# robotic_arm.net
KiCad netlist of a schematic drawn in EAGLE
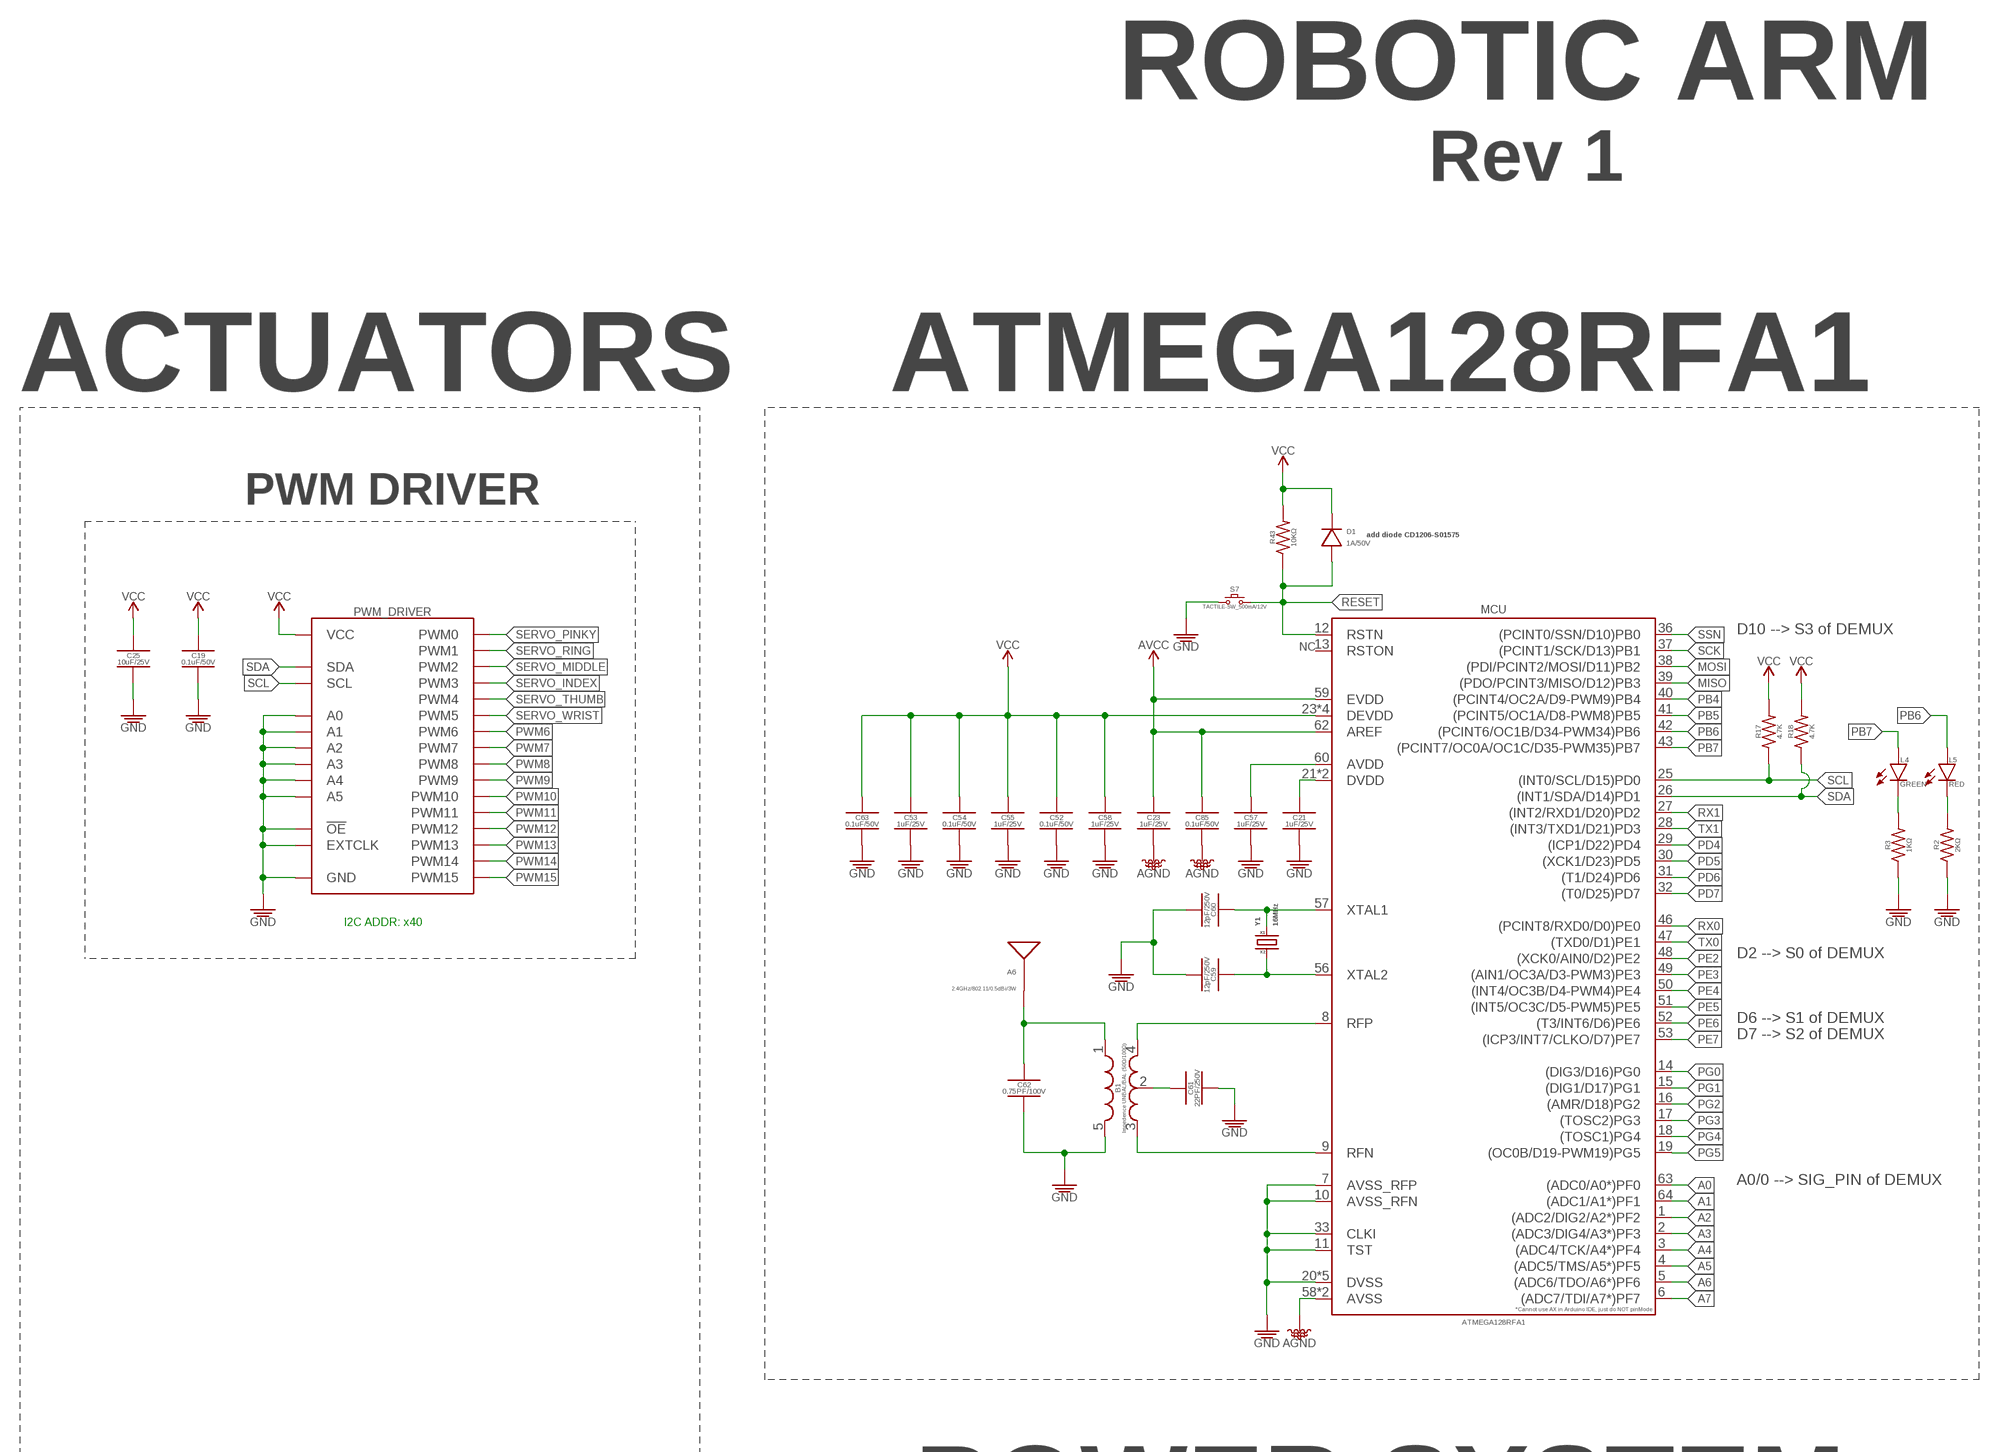
[diagram p0: schematic, sheet 1, part 1 of 3]
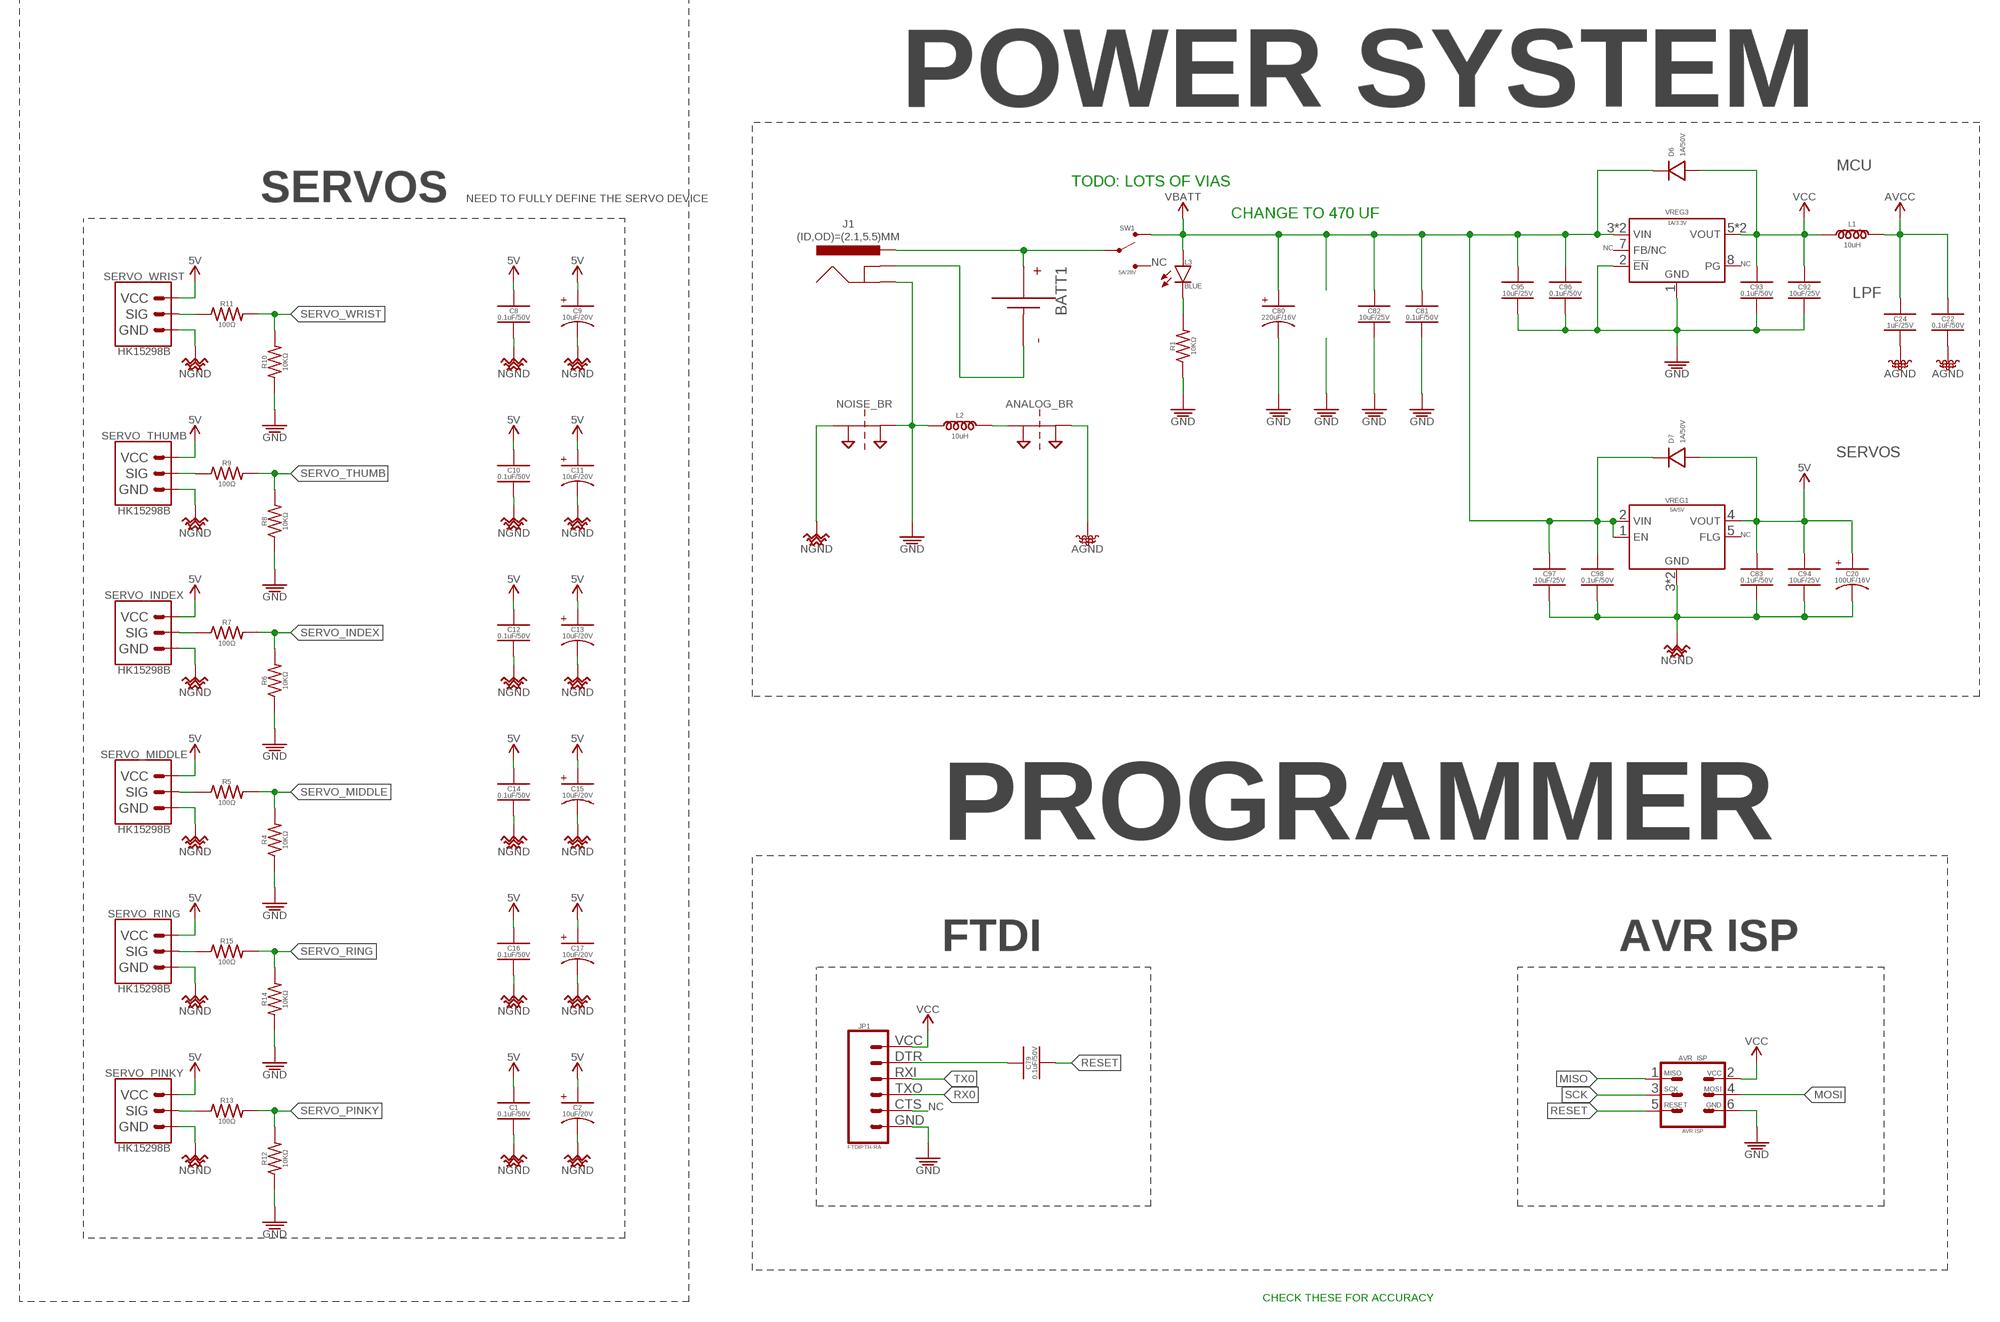
[diagram p1: schematic, sheet 1, part 2 of 3]
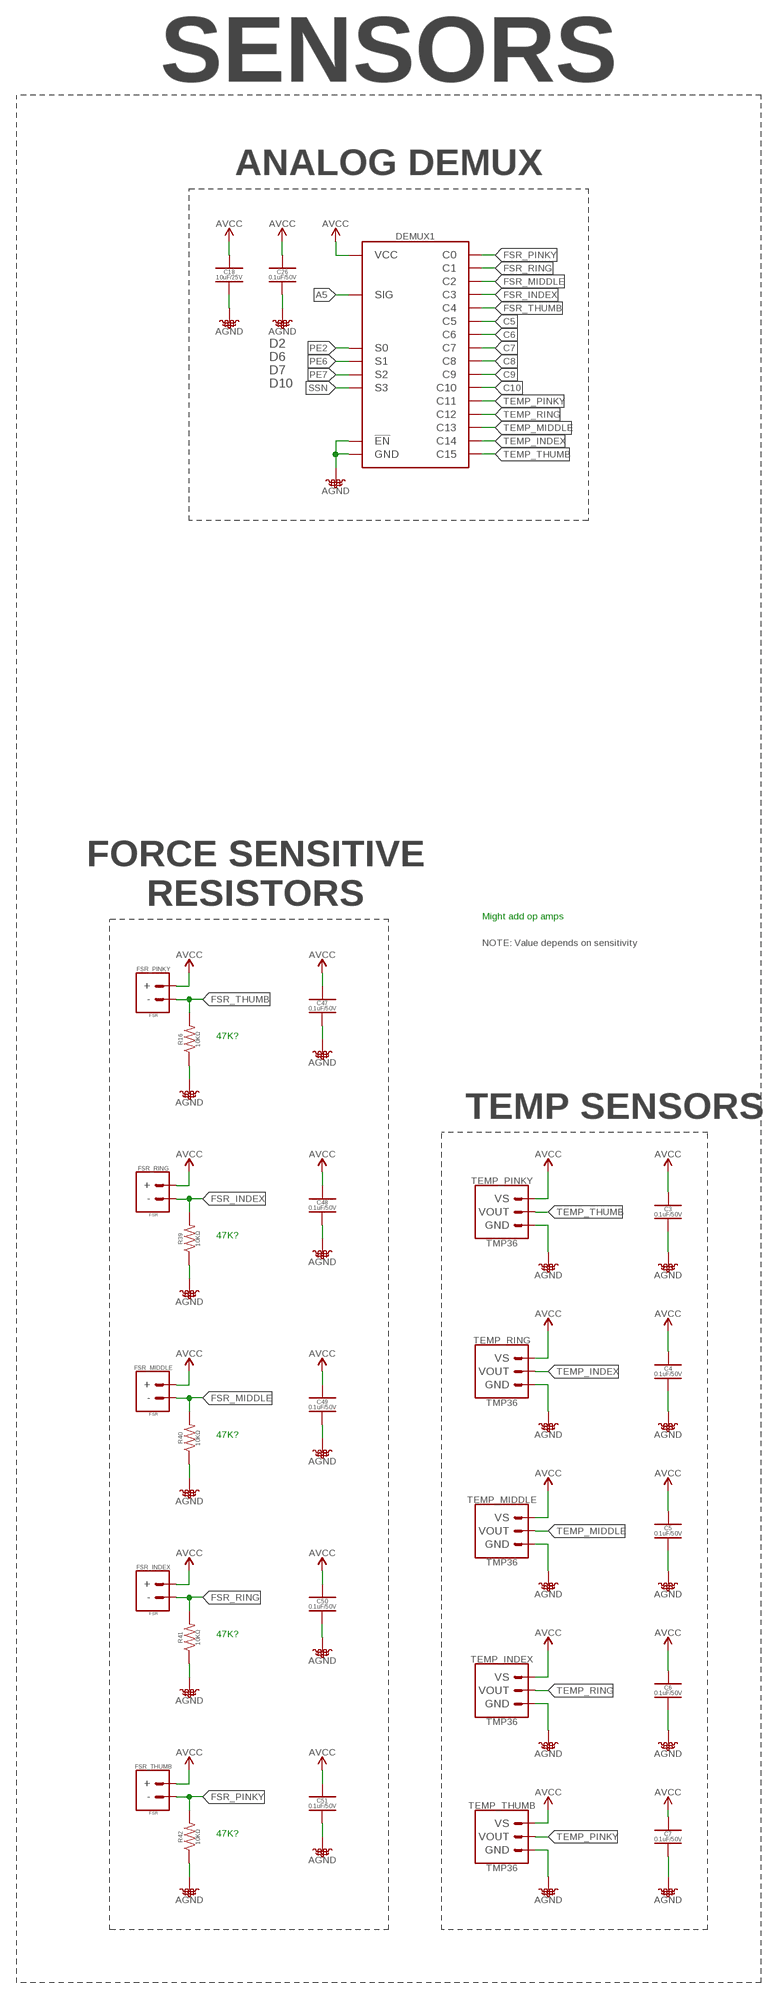
[diagram p2: schematic, sheet 1, part 3 of 3]

(export (version "E")
  (design (tool "Eeschema 10.0.6"))
  (components
    (comp (ref "A6")
      (value "2.4GHz/802.11/0.5dBi/3W")
      (footprint "eagle-import:ANTENNA-CHIP5")
      (fields
        (field (name "MFR") "Linx Technologies Inc.")
        (field (name "MPN") "ANT-2.45-CHP-T")
        (field (name "CREATOR") "Kenmei")
      )
      (libsource (lib "eagle-import") (part "ANTENNA_SMD-CHIP_2.4GHZ-0.5DBI-3W"))
    )
    (comp (ref "ANALOG_BR")
      (value "2PT_GND_TIE")
      (footprint "eagle-import:2PT_GND_TIE")
      (libsource (lib "eagle-import") (part "2PT_GND_TIE"))
    )
    (comp (ref "AVR_ISP")
      (value "AVR ISP")
      (footprint "eagle-import:2X3-NS")
      (fields (field (name "MFR") "Amphenol FCI") (field (name "MPN") "67997-206HLF"))
      (libsource (lib "eagle-import") (part "AVR_SPI_PRG_6NS"))
    )
    (comp (ref "B1")
      (value "Impedence UNBAL/BAL (50Ω/100Ω)")
      (footprint "eagle-import:0805_BALUN")
      (fields
        (field (name "MFR") "Wurth Electronics Inc")
        (field (name "MPN") "748421245")
        (field (name "CREATOR") "Kenmei")
      )
      (libsource (lib "eagle-import") (part "BALUN_SMD-0805_UNBAL/BAL-50/100"))
    )
    (comp (ref "BATT1")
      (value "BATTERYPTH_HOLES")
      (footprint "eagle-import:DUAL_PTH_PADS")
      (libsource (lib "eagle-import") (part "BATTERYPTH_HOLES"))
    )
    (comp (ref "C1")
      (value "0.1uF/50V")
      (footprint "eagle-import:_CER_SMD-805")
      (fields
        (field (name "MFR") "Murata Electronics North America")
        (field (name "MPN") "GRM21BR71H104KA01L")
        (field (name "CREATOR") "MrSwirlyEyes")
      )
      (libsource (lib "eagle-import") (part "0.1UF_SMD-805_50V-10%"))
    )
    (comp (ref "C2")
      (value "10uF/20V")
      (footprint "eagle-import:_TANT_SMD-1206")
      (fields
        (field (name "MFR") "AVX Corporation")
        (field (name "MPN") "TCJA106M020R0150")
        (field (name "CREATOR") "Kenmei")
      )
      (libsource (lib "eagle-import") (part "10UF-POLARIZED_SMD-1206_20V-20%"))
    )
    (comp (ref "C3")
      (value "0.1uF/50V")
      (footprint "eagle-import:_CER_SMD-805")
      (fields
        (field (name "MFR") "Murata Electronics North America")
        (field (name "MPN") "GRM21BR71H104KA01L")
        (field (name "CREATOR") "MrSwirlyEyes")
      )
      (libsource (lib "eagle-import") (part "0.1UF_SMD-805_50V-10%"))
    )
    (comp (ref "C4")
      (value "0.1uF/50V")
      (footprint "eagle-import:_CER_SMD-805")
      (fields
        (field (name "MFR") "Murata Electronics North America")
        (field (name "MPN") "GRM21BR71H104KA01L")
        (field (name "CREATOR") "MrSwirlyEyes")
      )
      (libsource (lib "eagle-import") (part "0.1UF_SMD-805_50V-10%"))
    )
    (comp (ref "C5")
      (value "0.1uF/50V")
      (footprint "eagle-import:_CER_SMD-805")
      (fields
        (field (name "MFR") "Murata Electronics North America")
        (field (name "MPN") "GRM21BR71H104KA01L")
        (field (name "CREATOR") "MrSwirlyEyes")
      )
      (libsource (lib "eagle-import") (part "0.1UF_SMD-805_50V-10%"))
    )
    (comp (ref "C6")
      (value "0.1uF/50V")
      (footprint "eagle-import:_CER_SMD-805")
      (fields
        (field (name "MFR") "Murata Electronics North America")
        (field (name "MPN") "GRM21BR71H104KA01L")
        (field (name "CREATOR") "MrSwirlyEyes")
      )
      (libsource (lib "eagle-import") (part "0.1UF_SMD-805_50V-10%"))
    )
    (comp (ref "C7")
      (value "0.1uF/50V")
      (footprint "eagle-import:_CER_SMD-805")
      (fields
        (field (name "MFR") "Murata Electronics North America")
        (field (name "MPN") "GRM21BR71H104KA01L")
        (field (name "CREATOR") "MrSwirlyEyes")
      )
      (libsource (lib "eagle-import") (part "0.1UF_SMD-805_50V-10%"))
    )
    (comp (ref "C8")
      (value "0.1uF/50V")
      (footprint "eagle-import:_CER_SMD-805")
      (fields
        (field (name "MFR") "Murata Electronics North America")
        (field (name "MPN") "GRM21BR71H104KA01L")
        (field (name "CREATOR") "MrSwirlyEyes")
      )
      (libsource (lib "eagle-import") (part "0.1UF_SMD-805_50V-10%"))
    )
    (comp (ref "C9")
      (value "10uF/20V")
      (footprint "eagle-import:_TANT_SMD-1206")
      (fields
        (field (name "MFR") "AVX Corporation")
        (field (name "MPN") "TCJA106M020R0150")
        (field (name "CREATOR") "Kenmei")
      )
      (libsource (lib "eagle-import") (part "10UF-POLARIZED_SMD-1206_20V-20%"))
    )
    (comp (ref "C10")
      (value "0.1uF/50V")
      (footprint "eagle-import:_CER_SMD-805")
      (fields
        (field (name "MFR") "Murata Electronics North America")
        (field (name "MPN") "GRM21BR71H104KA01L")
        (field (name "CREATOR") "MrSwirlyEyes")
      )
      (libsource (lib "eagle-import") (part "0.1UF_SMD-805_50V-10%"))
    )
    (comp (ref "C11")
      (value "10uF/20V")
      (footprint "eagle-import:_TANT_SMD-1206")
      (fields
        (field (name "MFR") "AVX Corporation")
        (field (name "MPN") "TCJA106M020R0150")
        (field (name "CREATOR") "Kenmei")
      )
      (libsource (lib "eagle-import") (part "10UF-POLARIZED_SMD-1206_20V-20%"))
    )
    (comp (ref "C12")
      (value "0.1uF/50V")
      (footprint "eagle-import:_CER_SMD-805")
      (fields
        (field (name "MFR") "Murata Electronics North America")
        (field (name "MPN") "GRM21BR71H104KA01L")
        (field (name "CREATOR") "MrSwirlyEyes")
      )
      (libsource (lib "eagle-import") (part "0.1UF_SMD-805_50V-10%"))
    )
    (comp (ref "C13")
      (value "10uF/20V")
      (footprint "eagle-import:_TANT_SMD-1206")
      (fields
        (field (name "MFR") "AVX Corporation")
        (field (name "MPN") "TCJA106M020R0150")
        (field (name "CREATOR") "Kenmei")
      )
      (libsource (lib "eagle-import") (part "10UF-POLARIZED_SMD-1206_20V-20%"))
    )
    (comp (ref "C14")
      (value "0.1uF/50V")
      (footprint "eagle-import:_CER_SMD-805")
      (fields
        (field (name "MFR") "Murata Electronics North America")
        (field (name "MPN") "GRM21BR71H104KA01L")
        (field (name "CREATOR") "MrSwirlyEyes")
      )
      (libsource (lib "eagle-import") (part "0.1UF_SMD-805_50V-10%"))
    )
    (comp (ref "C15")
      (value "10uF/20V")
      (footprint "eagle-import:_TANT_SMD-1206")
      (fields
        (field (name "MFR") "AVX Corporation")
        (field (name "MPN") "TCJA106M020R0150")
        (field (name "CREATOR") "Kenmei")
      )
      (libsource (lib "eagle-import") (part "10UF-POLARIZED_SMD-1206_20V-20%"))
    )
    (comp (ref "C16")
      (value "0.1uF/50V")
      (footprint "eagle-import:_CER_SMD-805")
      (fields
        (field (name "MFR") "Murata Electronics North America")
        (field (name "MPN") "GRM21BR71H104KA01L")
        (field (name "CREATOR") "MrSwirlyEyes")
      )
      (libsource (lib "eagle-import") (part "0.1UF_SMD-805_50V-10%"))
    )
    (comp (ref "C17")
      (value "10uF/20V")
      (footprint "eagle-import:_TANT_SMD-1206")
      (fields
        (field (name "MFR") "AVX Corporation")
        (field (name "MPN") "TCJA106M020R0150")
        (field (name "CREATOR") "Kenmei")
      )
      (libsource (lib "eagle-import") (part "10UF-POLARIZED_SMD-1206_20V-20%"))
    )
    (comp (ref "C18")
      (value "10uF/25V")
      (footprint "eagle-import:_CER_SMD-805")
      (fields
        (field (name "MFR") "Murata Electronics North America")
        (field (name "MPN") "GRM21BR61E106KA73K")
        (field (name "CREATOR") "MrSwirlyEyes")
      )
      (libsource (lib "eagle-import") (part "10UF_CER_SMD-805_25V-10%"))
    )
    (comp (ref "C19")
      (value "0.1uF/50V")
      (footprint "eagle-import:_CER_SMD-805")
      (fields
        (field (name "MFR") "Murata Electronics North America")
        (field (name "MPN") "GRM21BR71H104KA01L")
        (field (name "CREATOR") "MrSwirlyEyes")
      )
      (libsource (lib "eagle-import") (part "0.1UF_SMD-805_50V-10%"))
    )
    (comp (ref "C20")
      (value "100UF/16V")
      (footprint "eagle-import:_AE_SMD_L6.6-W6.6")
      (fields
        (field (name "MFR") "Panasonic Electronic Components")
        (field (name "MPN") "EEE-FK1C101P")
        (field (name "CREATOR") "MrSwirlyEyes")
      )
      (libsource (lib "eagle-import") (part "100UF-POLARIZED_SMD_16V-20%"))
    )
    (comp (ref "C21")
      (value "1uF/25V")
      (footprint "eagle-import:_CER_SMD-805")
      (fields
        (field (name "MFR") "Murata Electronics North America ")
        (field (name "MPN") "GRM216R61E105KA12D ")
        (field (name "CREATOR") "Kenmei")
      )
      (libsource (lib "eagle-import") (part "1UF_SMD-805_25V-10%"))
    )
    (comp (ref "C22")
      (value "0.1uF/50V")
      (footprint "eagle-import:_CER_SMD-805")
      (fields
        (field (name "MFR") "Murata Electronics North America")
        (field (name "MPN") "GRM21BR71H104KA01L")
        (field (name "CREATOR") "MrSwirlyEyes")
      )
      (libsource (lib "eagle-import") (part "0.1UF_SMD-805_50V-10%"))
    )
    (comp (ref "C23")
      (value "1uF/25V")
      (footprint "eagle-import:_CER_SMD-805")
      (fields
        (field (name "MFR") "Murata Electronics North America ")
        (field (name "MPN") "GRM216R61E105KA12D ")
        (field (name "CREATOR") "Kenmei")
      )
      (libsource (lib "eagle-import") (part "1UF_SMD-805_25V-10%"))
    )
    (comp (ref "C24")
      (value "1uF/25V")
      (footprint "eagle-import:_CER_SMD-805")
      (fields
        (field (name "MFR") "Murata Electronics North America ")
        (field (name "MPN") "GRM216R61E105KA12D ")
        (field (name "CREATOR") "Kenmei")
      )
      (libsource (lib "eagle-import") (part "1UF_SMD-805_25V-10%"))
    )
    (comp (ref "C25")
      (value "10uF/25V")
      (footprint "eagle-import:_CER_SMD-805")
      (fields
        (field (name "MFR") "Murata Electronics North America")
        (field (name "MPN") "GRM21BR61E106KA73K")
        (field (name "CREATOR") "MrSwirlyEyes")
      )
      (libsource (lib "eagle-import") (part "10UF_CER_SMD-805_25V-10%"))
    )
    (comp (ref "C26")
      (value "0.1uF/50V")
      (footprint "eagle-import:_CER_SMD-805")
      (fields
        (field (name "MFR") "Murata Electronics North America")
        (field (name "MPN") "GRM21BR71H104KA01L")
        (field (name "CREATOR") "MrSwirlyEyes")
      )
      (libsource (lib "eagle-import") (part "0.1UF_SMD-805_50V-10%"))
    )
    (comp (ref "C47")
      (value "0.1uF/50V")
      (footprint "eagle-import:_CER_SMD-805")
      (fields
        (field (name "MFR") "Murata Electronics North America")
        (field (name "MPN") "GRM21BR71H104KA01L")
        (field (name "CREATOR") "MrSwirlyEyes")
      )
      (libsource (lib "eagle-import") (part "0.1UF_SMD-805_50V-10%"))
    )
    (comp (ref "C48")
      (value "0.1uF/50V")
      (footprint "eagle-import:_CER_SMD-805")
      (fields
        (field (name "MFR") "Murata Electronics North America")
        (field (name "MPN") "GRM21BR71H104KA01L")
        (field (name "CREATOR") "MrSwirlyEyes")
      )
      (libsource (lib "eagle-import") (part "0.1UF_SMD-805_50V-10%"))
    )
    (comp (ref "C49")
      (value "0.1uF/50V")
      (footprint "eagle-import:_CER_SMD-805")
      (fields
        (field (name "MFR") "Murata Electronics North America")
        (field (name "MPN") "GRM21BR71H104KA01L")
        (field (name "CREATOR") "MrSwirlyEyes")
      )
      (libsource (lib "eagle-import") (part "0.1UF_SMD-805_50V-10%"))
    )
    (comp (ref "C50")
      (value "0.1uF/50V")
      (footprint "eagle-import:_CER_SMD-805")
      (fields
        (field (name "MFR") "Murata Electronics North America")
        (field (name "MPN") "GRM21BR71H104KA01L")
        (field (name "CREATOR") "MrSwirlyEyes")
      )
      (libsource (lib "eagle-import") (part "0.1UF_SMD-805_50V-10%"))
    )
    (comp (ref "C51")
      (value "0.1uF/50V")
      (footprint "eagle-import:_CER_SMD-805")
      (fields
        (field (name "MFR") "Murata Electronics North America")
        (field (name "MPN") "GRM21BR71H104KA01L")
        (field (name "CREATOR") "MrSwirlyEyes")
      )
      (libsource (lib "eagle-import") (part "0.1UF_SMD-805_50V-10%"))
    )
    (comp (ref "C52")
      (value "0.1uF/50V")
      (footprint "eagle-import:_CER_SMD-805")
      (fields
        (field (name "MFR") "Murata Electronics North America")
        (field (name "MPN") "GRM21BR71H104KA01L")
        (field (name "CREATOR") "MrSwirlyEyes")
      )
      (libsource (lib "eagle-import") (part "0.1UF_SMD-805_50V-10%"))
    )
    (comp (ref "C53")
      (value "1uF/25V")
      (footprint "eagle-import:_CER_SMD-805")
      (fields
        (field (name "MFR") "Murata Electronics North America ")
        (field (name "MPN") "GRM216R61E105KA12D ")
        (field (name "CREATOR") "Kenmei")
      )
      (libsource (lib "eagle-import") (part "1UF_SMD-805_25V-10%"))
    )
    (comp (ref "C54")
      (value "0.1uF/50V")
      (footprint "eagle-import:_CER_SMD-805")
      (fields
        (field (name "MFR") "Murata Electronics North America")
        (field (name "MPN") "GRM21BR71H104KA01L")
        (field (name "CREATOR") "MrSwirlyEyes")
      )
      (libsource (lib "eagle-import") (part "0.1UF_SMD-805_50V-10%"))
    )
    (comp (ref "C55")
      (value "1uF/25V")
      (footprint "eagle-import:_CER_SMD-805")
      (fields
        (field (name "MFR") "Murata Electronics North America ")
        (field (name "MPN") "GRM216R61E105KA12D ")
        (field (name "CREATOR") "Kenmei")
      )
      (libsource (lib "eagle-import") (part "1UF_SMD-805_25V-10%"))
    )
    (comp (ref "C57")
      (value "1uF/25V")
      (footprint "eagle-import:_CER_SMD-805")
      (fields
        (field (name "MFR") "Murata Electronics North America ")
        (field (name "MPN") "GRM216R61E105KA12D ")
        (field (name "CREATOR") "Kenmei")
      )
      (libsource (lib "eagle-import") (part "1UF_SMD-805_25V-10%"))
    )
    (comp (ref "C58")
      (value "1uF/25V")
      (footprint "eagle-import:_CER_SMD-805")
      (fields
        (field (name "MFR") "Murata Electronics North America ")
        (field (name "MPN") "GRM216R61E105KA12D ")
        (field (name "CREATOR") "Kenmei")
      )
      (libsource (lib "eagle-import") (part "1UF_SMD-805_25V-10%"))
    )
    (comp (ref "C59")
      (value "12pF/250V")
      (footprint "eagle-import:_CER_SMD-805")
      (fields
        (field (name "MFR") "Murata Electronics North America")
        (field (name "MPN") "GRM21A5C2E120JW01D ")
        (field (name "CREATOR") "Kenmei")
      )
      (libsource (lib "eagle-import") (part "12PF_SMD-805_250V-5%"))
    )
    (comp (ref "C60")
      (value "12pF/250V")
      (footprint "eagle-import:_CER_SMD-805")
      (fields
        (field (name "MFR") "Murata Electronics North America")
        (field (name "MPN") "GRM21A5C2E120JW01D ")
        (field (name "CREATOR") "Kenmei")
      )
      (libsource (lib "eagle-import") (part "12PF_SMD-805_250V-5%"))
    )
    (comp (ref "C61")
      (value "22PF/250V")
      (footprint "eagle-import:_CER_SMD-805")
      (fields
        (field (name "MFR") "Murata Electronics North America ")
        (field (name "MPN") "GRM21A5C2E220JW01D ")
        (field (name "CREATOR") "Kenmei")
      )
      (libsource (lib "eagle-import") (part "22PF_SMD-805_250V-5%"))
    )
    (comp (ref "C62")
      (value "0.75PF/100V")
      (footprint "eagle-import:_CER_SMD-805")
      (fields
        (field (name "MFR") "Murata Electronics North America ")
        (field (name "MPN") "GQM2195C2AR75CB01D ")
        (field (name "CREATOR") "Kenmei")
      )
      (libsource (lib "eagle-import") (part "0.75PF_SMD-805_100V-33%"))
    )
    (comp (ref "C63")
      (value "0.1uF/50V")
      (footprint "eagle-import:_CER_SMD-805")
      (fields
        (field (name "MFR") "Murata Electronics North America")
        (field (name "MPN") "GRM21BR71H104KA01L")
        (field (name "CREATOR") "MrSwirlyEyes")
      )
      (libsource (lib "eagle-import") (part "0.1UF_SMD-805_50V-10%"))
    )
    (comp (ref "C79")
      (value "0.1uF/50V")
      (footprint "eagle-import:_CER_SMD-805")
      (fields
        (field (name "MFR") "Murata Electronics North America")
        (field (name "MPN") "GRM21BR71H104KA01L")
        (field (name "CREATOR") "MrSwirlyEyes")
      )
      (libsource (lib "eagle-import") (part "0.1UF_SMD-805_50V-10%"))
    )
    (comp (ref "C80")
      (value "220uF/16V")
      (footprint "eagle-import:_AE_SMD_L6.6-W6.6")
      (fields
        (field (name "MFR") "Panasonic Electronic Components")
        (field (name "MPN") "EEE-FT1C221AP")
        (field (name "CREATOR") "MrSwirlyEyes")
      )
      (libsource (lib "eagle-import") (part "220UF-POLARIZED_SMD_16V-20%"))
    )
    (comp (ref "C81")
      (value "0.1uF/50V")
      (footprint "eagle-import:_CER_SMD-805")
      (fields
        (field (name "MFR") "Murata Electronics North America")
        (field (name "MPN") "GRM21BR71H104KA01L")
        (field (name "CREATOR") "MrSwirlyEyes")
      )
      (libsource (lib "eagle-import") (part "0.1UF_SMD-805_50V-10%"))
    )
    (comp (ref "C82")
      (value "10uF/25V")
      (footprint "eagle-import:_CER_SMD-805")
      (fields
        (field (name "MFR") "Murata Electronics North America")
        (field (name "MPN") "GRM21BR61E106KA73K")
        (field (name "CREATOR") "MrSwirlyEyes")
      )
      (libsource (lib "eagle-import") (part "10UF_CER_SMD-805_25V-10%"))
    )
    (comp (ref "C83")
      (value "0.1uF/50V")
      (footprint "eagle-import:_CER_SMD-805")
      (fields
        (field (name "MFR") "Murata Electronics North America")
        (field (name "MPN") "GRM21BR71H104KA01L")
        (field (name "CREATOR") "MrSwirlyEyes")
      )
      (libsource (lib "eagle-import") (part "0.1UF_SMD-805_50V-10%"))
    )
    (comp (ref "C85")
      (value "0.1uF/50V")
      (footprint "eagle-import:_CER_SMD-805")
      (fields
        (field (name "MFR") "Murata Electronics North America")
        (field (name "MPN") "GRM21BR71H104KA01L")
        (field (name "CREATOR") "MrSwirlyEyes")
      )
      (libsource (lib "eagle-import") (part "0.1UF_SMD-805_50V-10%"))
    )
    (comp (ref "C92")
      (value "10uF/25V")
      (footprint "eagle-import:_CER_SMD-805")
      (fields
        (field (name "MFR") "Murata Electronics North America")
        (field (name "MPN") "GRM21BR61E106KA73K")
        (field (name "CREATOR") "MrSwirlyEyes")
      )
      (libsource (lib "eagle-import") (part "10UF_CER_SMD-805_25V-10%"))
    )
    (comp (ref "C93")
      (value "0.1uF/50V")
      (footprint "eagle-import:_CER_SMD-805")
      (fields
        (field (name "MFR") "Murata Electronics North America")
        (field (name "MPN") "GRM21BR71H104KA01L")
        (field (name "CREATOR") "MrSwirlyEyes")
      )
      (libsource (lib "eagle-import") (part "0.1UF_SMD-805_50V-10%"))
    )
    (comp (ref "C94")
      (value "10uF/25V")
      (footprint "eagle-import:_CER_SMD-805")
      (fields
        (field (name "MFR") "Murata Electronics North America")
        (field (name "MPN") "GRM21BR61E106KA73K")
        (field (name "CREATOR") "MrSwirlyEyes")
      )
      (libsource (lib "eagle-import") (part "10UF_CER_SMD-805_25V-10%"))
    )
    (comp (ref "C95")
      (value "10uF/25V")
      (footprint "eagle-import:_CER_SMD-805")
      (fields
        (field (name "MFR") "Murata Electronics North America")
        (field (name "MPN") "GRM21BR61E106KA73K")
        (field (name "CREATOR") "MrSwirlyEyes")
      )
      (libsource (lib "eagle-import") (part "10UF_CER_SMD-805_25V-10%"))
    )
    (comp (ref "C96")
      (value "0.1uF/50V")
      (footprint "eagle-import:_CER_SMD-805")
      (fields
        (field (name "MFR") "Murata Electronics North America")
        (field (name "MPN") "GRM21BR71H104KA01L")
        (field (name "CREATOR") "MrSwirlyEyes")
      )
      (libsource (lib "eagle-import") (part "0.1UF_SMD-805_50V-10%"))
    )
    (comp (ref "C97")
      (value "10uF/25V")
      (footprint "eagle-import:_CER_SMD-805")
      (fields
        (field (name "MFR") "Murata Electronics North America")
        (field (name "MPN") "GRM21BR61E106KA73K")
        (field (name "CREATOR") "MrSwirlyEyes")
      )
      (libsource (lib "eagle-import") (part "10UF_CER_SMD-805_25V-10%"))
    )
    (comp (ref "C98")
      (value "0.1uF/50V")
      (footprint "eagle-import:_CER_SMD-805")
      (fields
        (field (name "MFR") "Murata Electronics North America")
        (field (name "MPN") "GRM21BR71H104KA01L")
        (field (name "CREATOR") "MrSwirlyEyes")
      )
      (libsource (lib "eagle-import") (part "0.1UF_SMD-805_50V-10%"))
    )
    (comp (ref "D1")
      (value "1A/50V")
      (footprint "eagle-import:SOD123F")
      (fields
        (field (name "MFR") "Comchip Technology")
        (field (name "MPN") "CGRKM4001-HF")
        (field (name "CREATOR") "MrSwirlyEyes")
      )
      (libsource (lib "eagle-import") (part "DIODE_GENERAL-PURPOSE_SMD_GP_1A-50V"))
    )
    (comp (ref "D6")
      (value "1A/50V")
      (footprint "eagle-import:SOD123F")
      (fields
        (field (name "MFR") "Comchip Technology")
        (field (name "MPN") "CGRKM4001-HF")
        (field (name "CREATOR") "MrSwirlyEyes")
      )
      (libsource (lib "eagle-import") (part "DIODE_GENERAL-PURPOSE_SMD_GP_1A-50V"))
    )
    (comp (ref "D7")
      (value "1A/50V")
      (footprint "eagle-import:SOD123F")
      (fields
        (field (name "MFR") "Comchip Technology")
        (field (name "MPN") "CGRKM4001-HF")
        (field (name "CREATOR") "MrSwirlyEyes")
      )
      (libsource (lib "eagle-import") (part "DIODE_GENERAL-PURPOSE_SMD_GP_1A-50V"))
    )
    (comp (ref "DEMUX1")
      (value "CH16_MUX-DEMUX")
      (footprint "eagle-import:SSOP-24")
      (fields
        (field (name "MFR") "Texas Instruments")
        (field (name "MPN") "CD74HC4067SM96")
        (field (name "CREATOR") "MrSwirlyEyes")
      )
      (libsource (lib "eagle-import") (part "CD74HC4067-SM96_16{colon}1_MUX-DEMUX"))
    )
    (comp (ref "FSR_INDEX")
      (value "FSR")
      (footprint "eagle-import:CONNECTOR_FSR")
      (fields
        (field (name "MFR") "Interlink Electronics")
        (field (name "MPN") "34-00004")
        (field (name "CREATOR") "MrSwirlyEyes")
      )
      (libsource (lib "eagle-import") (part "FSR_FORCE-SENSATIVE-RESISTOR_PRESS-SENSOR"))
    )
    (comp (ref "FSR_MIDDLE")
      (value "FSR")
      (footprint "eagle-import:CONNECTOR_FSR")
      (fields
        (field (name "MFR") "Interlink Electronics")
        (field (name "MPN") "34-00004")
        (field (name "CREATOR") "MrSwirlyEyes")
      )
      (libsource (lib "eagle-import") (part "FSR_FORCE-SENSATIVE-RESISTOR_PRESS-SENSOR"))
    )
    (comp (ref "FSR_PINKY")
      (value "FSR")
      (footprint "eagle-import:CONNECTOR_FSR")
      (fields
        (field (name "MFR") "Interlink Electronics")
        (field (name "MPN") "34-00004")
        (field (name "CREATOR") "MrSwirlyEyes")
      )
      (libsource (lib "eagle-import") (part "FSR_FORCE-SENSATIVE-RESISTOR_PRESS-SENSOR"))
    )
    (comp (ref "FSR_RING")
      (value "FSR")
      (footprint "eagle-import:CONNECTOR_FSR")
      (fields
        (field (name "MFR") "Interlink Electronics")
        (field (name "MPN") "34-00004")
        (field (name "CREATOR") "MrSwirlyEyes")
      )
      (libsource (lib "eagle-import") (part "FSR_FORCE-SENSATIVE-RESISTOR_PRESS-SENSOR"))
    )
    (comp (ref "FSR_THUMB")
      (value "FSR")
      (footprint "eagle-import:CONNECTOR_FSR")
      (fields
        (field (name "MFR") "Interlink Electronics")
        (field (name "MPN") "34-00004")
        (field (name "CREATOR") "MrSwirlyEyes")
      )
      (libsource (lib "eagle-import") (part "FSR_FORCE-SENSATIVE-RESISTOR_PRESS-SENSOR"))
    )
    (comp (ref "J1")
      (value "(ID,OD)=(2.1,5.5)MM")
      (footprint "eagle-import:POWER_JACK_SLOT_ID2.1MM-OD5.5MM")
      (fields
        (field (name "MFR") "MPD (Memory Protection Devices)")
        (field (name "MPN") "EJ508A")
        (field (name "CREATOR") "MrSwirlyEyes")
      )
      (libsource (lib "eagle-import") (part "POWER_JACK-BARREL_ID2.1MM-OD5.5MM"))
    )
    (comp (ref "JP1")
      (value "FTDIPTH-RA")
      (footprint "eagle-import:FTDI_BASIC-6PIN-MALE-RA")
      (fields (field (name "MFR") "Amphenol FCI") (field (name "MPN") "68016-406HLF"))
      (libsource (lib "eagle-import") (part "FTDIPTH-RA"))
    )
    (comp (ref "L1")
      (value "10uH")
      (footprint "eagle-import:_SMD-805")
      (fields
        (field (name "MFR") "Taiyo Yuden")
        (field (name "MPN") "CB2012T100KR")
        (field (name "CREATOR") "MrSwirlyEyes")
      )
      (libsource (lib "eagle-import") (part "10UH_SMD-805_0.5A-0.65OHM-10%"))
    )
    (comp (ref "L2")
      (value "10uH")
      (footprint "eagle-import:_SMD-805")
      (fields
        (field (name "MFR") "Taiyo Yuden")
        (field (name "MPN") "CB2012T100KR")
        (field (name "CREATOR") "MrSwirlyEyes")
      )
      (libsource (lib "eagle-import") (part "10UH_SMD-805_0.5A-0.65OHM-10%"))
    )
    (comp (ref "L3")
      (value "BLUE")
      (footprint "eagle-import:LED_SMD-805_")
      (fields
        (field (name "MFR") "Lite-On Inc.")
        (field (name "MPN") "LTST-C170TBKT")
        (field (name "CREATOR") "MrSwirlyEyes")
      )
      (libsource (lib "eagle-import") (part "LED_SMD-0805_DISCRETE_BLUE"))
    )
    (comp (ref "L4")
      (value "GREEN")
      (footprint "eagle-import:LED_SMD-805_")
      (fields
        (field (name "MFR") "Lite-On Inc.")
        (field (name "MPN") "LTST-C170KGKT")
        (field (name "CREATOR") "MrSwirlyEyes")
      )
      (libsource (lib "eagle-import") (part "LED_SMD-0805_DISCRETE_GREEN"))
    )
    (comp (ref "L5")
      (value "RED")
      (footprint "eagle-import:LED_SMD-805_")
      (fields
        (field (name "MFR") "Lite-On Inc.")
        (field (name "MPN") "LTST-C170KRKT")
        (field (name "CREATOR") "MrSwirlyEyes")
      )
      (libsource (lib "eagle-import") (part "LED_SMD-0805_DISCRETE_RED"))
    )
    (comp (ref "MCU")
      (value "ATMEGA128RFA1")
      (footprint "eagle-import:VFQFN-64")
      (fields
        (field (name "MFR") "Atmel")
        (field (name "MPN") "ATMEGA128RFA1-ZU ")
        (field (name "CREATOR") "Kenmei")
      )
      (libsource (lib "eagle-import") (part "ATMEGA128RFA1_VFQFN-64_EXPOSED-PAD"))
    )
    (comp (ref "NOISE_BR")
      (value "2PT_GND_TIE")
      (footprint "eagle-import:2PT_GND_TIE")
      (libsource (lib "eagle-import") (part "2PT_GND_TIE"))
    )
    (comp (ref "PWM_DRIVER")
      (value "PCA9685")
      (footprint "eagle-import:TSSOP-28")
      (fields
        (field (name "MFR") "NXP USA Inc.")
        (field (name "MPN") "PCA9685PW,118")
        (field (name "CREATOR") "MrSwirlyEyes")
      )
      (libsource (lib "eagle-import") (part "PCA9685_16-CH_12-BIT_PWM-DRIVER"))
    )
    (comp (ref "R1")
      (value "10KΩ")
      (footprint "eagle-import:RESISTOR_SMD-805")
      (fields
        (field (name "MFR") "Yageo")
        (field (name "MPN") "RC0805JR-0710KL")
        (field (name "CREATOR") "Kenmei")
      )
      (libsource (lib "eagle-import") (part "10KΩ_SMD-0805_1/8W-5%"))
    )
    (comp (ref "R2")
      (value "2KΩ")
      (footprint "eagle-import:RESISTOR_SMD-805")
      (fields
        (field (name "MFR") "Yageo")
        (field (name "MPN") "RC0805JR-072KL")
        (field (name "CREATOR") "MrSwirlyEyes")
      )
      (libsource (lib "eagle-import") (part "2KΩ_SMD-0805_1/8W-5%"))
    )
    (comp (ref "R3")
      (value "1KΩ")
      (footprint "eagle-import:RESISTOR_SMD-805")
      (fields
        (field (name "MFR") "Yageo")
        (field (name "MPN") "RC0805JR-071KL ")
        (field (name "CREATOR") "Kenmei")
      )
      (libsource (lib "eagle-import") (part "1KΩ_SMD-0805_1/8W-5%"))
    )
    (comp (ref "R4")
      (value "10KΩ")
      (footprint "eagle-import:RESISTOR_SMD-805")
      (fields
        (field (name "MFR") "Yageo")
        (field (name "MPN") "RC0805JR-0710KL")
        (field (name "CREATOR") "Kenmei")
      )
      (libsource (lib "eagle-import") (part "10KΩ_SMD-0805_1/8W-5%"))
    )
    (comp (ref "R5")
      (value "100Ω")
      (footprint "eagle-import:RESISTOR_SMD-805")
      (fields
        (field (name "MFR") "Yageo")
        (field (name "MPN") "RC0805JR-07100RL")
        (field (name "CREATOR") "Kenmei")
      )
      (libsource (lib "eagle-import") (part "100Ω_SMD-0805_1/8W-5%"))
    )
    (comp (ref "R6")
      (value "10KΩ")
      (footprint "eagle-import:RESISTOR_SMD-805")
      (fields
        (field (name "MFR") "Yageo")
        (field (name "MPN") "RC0805JR-0710KL")
        (field (name "CREATOR") "Kenmei")
      )
      (libsource (lib "eagle-import") (part "10KΩ_SMD-0805_1/8W-5%"))
    )
    (comp (ref "R7")
      (value "100Ω")
      (footprint "eagle-import:RESISTOR_SMD-805")
      (fields
        (field (name "MFR") "Yageo")
        (field (name "MPN") "RC0805JR-07100RL")
        (field (name "CREATOR") "Kenmei")
      )
      (libsource (lib "eagle-import") (part "100Ω_SMD-0805_1/8W-5%"))
    )
    (comp (ref "R8")
      (value "10KΩ")
      (footprint "eagle-import:RESISTOR_SMD-805")
      (fields
        (field (name "MFR") "Yageo")
        (field (name "MPN") "RC0805JR-0710KL")
        (field (name "CREATOR") "Kenmei")
      )
      (libsource (lib "eagle-import") (part "10KΩ_SMD-0805_1/8W-5%"))
    )
    (comp (ref "R9")
      (value "100Ω")
      (footprint "eagle-import:RESISTOR_SMD-805")
      (fields
        (field (name "MFR") "Yageo")
        (field (name "MPN") "RC0805JR-07100RL")
        (field (name "CREATOR") "Kenmei")
      )
      (libsource (lib "eagle-import") (part "100Ω_SMD-0805_1/8W-5%"))
    )
    (comp (ref "R10")
      (value "10KΩ")
      (footprint "eagle-import:RESISTOR_SMD-805")
      (fields
        (field (name "MFR") "Yageo")
        (field (name "MPN") "RC0805JR-0710KL")
        (field (name "CREATOR") "Kenmei")
      )
      (libsource (lib "eagle-import") (part "10KΩ_SMD-0805_1/8W-5%"))
    )
    (comp (ref "R11")
      (value "100Ω")
      (footprint "eagle-import:RESISTOR_SMD-805")
      (fields
        (field (name "MFR") "Yageo")
        (field (name "MPN") "RC0805JR-07100RL")
        (field (name "CREATOR") "Kenmei")
      )
      (libsource (lib "eagle-import") (part "100Ω_SMD-0805_1/8W-5%"))
    )
    (comp (ref "R12")
      (value "10KΩ")
      (footprint "eagle-import:RESISTOR_SMD-805")
      (fields
        (field (name "MFR") "Yageo")
        (field (name "MPN") "RC0805JR-0710KL")
        (field (name "CREATOR") "Kenmei")
      )
      (libsource (lib "eagle-import") (part "10KΩ_SMD-0805_1/8W-5%"))
    )
    (comp (ref "R13")
      (value "100Ω")
      (footprint "eagle-import:RESISTOR_SMD-805")
      (fields
        (field (name "MFR") "Yageo")
        (field (name "MPN") "RC0805JR-07100RL")
        (field (name "CREATOR") "Kenmei")
      )
      (libsource (lib "eagle-import") (part "100Ω_SMD-0805_1/8W-5%"))
    )
    (comp (ref "R14")
      (value "10KΩ")
      (footprint "eagle-import:RESISTOR_SMD-805")
      (fields
        (field (name "MFR") "Yageo")
        (field (name "MPN") "RC0805JR-0710KL")
        (field (name "CREATOR") "Kenmei")
      )
      (libsource (lib "eagle-import") (part "10KΩ_SMD-0805_1/8W-5%"))
    )
    (comp (ref "R15")
      (value "100Ω")
      (footprint "eagle-import:RESISTOR_SMD-805")
      (fields
        (field (name "MFR") "Yageo")
        (field (name "MPN") "RC0805JR-07100RL")
        (field (name "CREATOR") "Kenmei")
      )
      (libsource (lib "eagle-import") (part "100Ω_SMD-0805_1/8W-5%"))
    )
    (comp (ref "R16")
      (value "10KΩ")
      (footprint "eagle-import:RESISTOR_SMD-805")
      (fields
        (field (name "MFR") "Yageo")
        (field (name "MPN") "RC0805JR-0710KL")
        (field (name "CREATOR") "Kenmei")
      )
      (libsource (lib "eagle-import") (part "10KΩ_SMD-0805_1/8W-5%"))
    )
    (comp (ref "R17")
      (value "4.7K")
      (footprint "eagle-import:RESISTOR_SMD-805")
      (fields
        (field (name "MFR") "Yageo")
        (field (name "MPN") "RC0805JR-074K7L")
        (field (name "CREATOR") "MrSwirlyEyes")
      )
      (libsource (lib "eagle-import") (part "4.7KΩ_SMD-0805_1/8W-5%"))
    )
    (comp (ref "R18")
      (value "4.7K")
      (footprint "eagle-import:RESISTOR_SMD-805")
      (fields
        (field (name "MFR") "Yageo")
        (field (name "MPN") "RC0805JR-074K7L")
        (field (name "CREATOR") "MrSwirlyEyes")
      )
      (libsource (lib "eagle-import") (part "4.7KΩ_SMD-0805_1/8W-5%"))
    )
    (comp (ref "R39")
      (value "10KΩ")
      (footprint "eagle-import:RESISTOR_SMD-805")
      (fields
        (field (name "MFR") "Yageo")
        (field (name "MPN") "RC0805JR-0710KL")
        (field (name "CREATOR") "Kenmei")
      )
      (libsource (lib "eagle-import") (part "10KΩ_SMD-0805_1/8W-5%"))
    )
    (comp (ref "R40")
      (value "10KΩ")
      (footprint "eagle-import:RESISTOR_SMD-805")
      (fields
        (field (name "MFR") "Yageo")
        (field (name "MPN") "RC0805JR-0710KL")
        (field (name "CREATOR") "Kenmei")
      )
      (libsource (lib "eagle-import") (part "10KΩ_SMD-0805_1/8W-5%"))
    )
    (comp (ref "R41")
      (value "10KΩ")
      (footprint "eagle-import:RESISTOR_SMD-805")
      (fields
        (field (name "MFR") "Yageo")
        (field (name "MPN") "RC0805JR-0710KL")
        (field (name "CREATOR") "Kenmei")
      )
      (libsource (lib "eagle-import") (part "10KΩ_SMD-0805_1/8W-5%"))
    )
    (comp (ref "R42")
      (value "10KΩ")
      (footprint "eagle-import:RESISTOR_SMD-805")
      (fields
        (field (name "MFR") "Yageo")
        (field (name "MPN") "RC0805JR-0710KL")
        (field (name "CREATOR") "Kenmei")
      )
      (libsource (lib "eagle-import") (part "10KΩ_SMD-0805_1/8W-5%"))
    )
    (comp (ref "R43")
      (value "10KΩ")
      (footprint "eagle-import:RESISTOR_SMD-805")
      (fields
        (field (name "MFR") "Yageo")
        (field (name "MPN") "RC0805JR-0710KL")
        (field (name "CREATOR") "Kenmei")
      )
      (libsource (lib "eagle-import") (part "10KΩ_SMD-0805_1/8W-5%"))
    )
    (comp (ref "S7")
      (value "TACTILE-SW_500mA/12V")
      (footprint "eagle-import:BTN_MOMENTARY_SPST-NO_SMD_12V_50MA_L5.2-W5.2")
      (fields
        (field (name "MFR") "C&K")
        (field (name "MPN") "RS-187R05A2-DS MT RT")
        (field (name "CREATOR") "MrSwirlyEyes")
      )
      (libsource (lib "eagle-import") (part "SWITCH_MOMENTARYSPST-SMD-50MA-12V_L5.2-W5.2"))
    )
    (comp (ref "SERVO_INDEX")
      (value "HK15298B")
      (footprint "eagle-import:CONNECTOR_SERVO")
      (fields (field (name "CREATOR") "MrSwirlyEyes"))
      (libsource (lib "eagle-import") (part "SERVO-HK15298B"))
    )
    (comp (ref "SERVO_MIDDLE")
      (value "HK15298B")
      (footprint "eagle-import:CONNECTOR_SERVO")
      (fields (field (name "CREATOR") "MrSwirlyEyes"))
      (libsource (lib "eagle-import") (part "SERVO-HK15298B"))
    )
    (comp (ref "SERVO_PINKY")
      (value "HK15298B")
      (footprint "eagle-import:CONNECTOR_SERVO")
      (fields (field (name "CREATOR") "MrSwirlyEyes"))
      (libsource (lib "eagle-import") (part "SERVO-HK15298B"))
    )
    (comp (ref "SERVO_RING")
      (value "HK15298B")
      (footprint "eagle-import:CONNECTOR_SERVO")
      (fields (field (name "CREATOR") "MrSwirlyEyes"))
      (libsource (lib "eagle-import") (part "SERVO-HK15298B"))
    )
    (comp (ref "SERVO_THUMB")
      (value "HK15298B")
      (footprint "eagle-import:CONNECTOR_SERVO")
      (fields (field (name "CREATOR") "MrSwirlyEyes"))
      (libsource (lib "eagle-import") (part "SERVO-HK15298B"))
    )
    (comp (ref "SERVO_WRIST")
      (value "HK15298B")
      (footprint "eagle-import:CONNECTOR_SERVO")
      (fields (field (name "CREATOR") "MrSwirlyEyes"))
      (libsource (lib "eagle-import") (part "SERVO-HK15298B"))
    )
    (comp (ref "SW1")
      (value "5A/28V")
      (footprint "eagle-import:SW_TOGGLE_SPDT_5A-28V_13L-7W")
      (fields
        (field (name "MFR") "E-Switch")
        (field (name "MPN") "100SP1T1B4M2QE")
        (field (name "CREATOR") "MrSwirlyEyes")
      )
      (libsource (lib "eagle-import") (part "SWITCH_SPDT_VERT_PTH_5A-28V_13L-7W"))
    )
    (comp (ref "TEMP_INDEX")
      (value "TMP36")
      (footprint "eagle-import:CONNECTOR_TMP36")
      (fields
        (field (name "MFR") "Analog Devices Inc.")
        (field (name "MPN") "TMP36GT9Z")
        (field (name "CREATOR") "MrSwirlyEyes")
      )
      (libsource (lib "eagle-import") (part "TEMPERATURE-SENSOR_TMP36"))
    )
    (comp (ref "TEMP_MIDDLE")
      (value "TMP36")
      (footprint "eagle-import:CONNECTOR_TMP36")
      (fields
        (field (name "MFR") "Analog Devices Inc.")
        (field (name "MPN") "TMP36GT9Z")
        (field (name "CREATOR") "MrSwirlyEyes")
      )
      (libsource (lib "eagle-import") (part "TEMPERATURE-SENSOR_TMP36"))
    )
    (comp (ref "TEMP_PINKY")
      (value "TMP36")
      (footprint "eagle-import:CONNECTOR_TMP36")
      (fields
        (field (name "MFR") "Analog Devices Inc.")
        (field (name "MPN") "TMP36GT9Z")
        (field (name "CREATOR") "MrSwirlyEyes")
      )
      (libsource (lib "eagle-import") (part "TEMPERATURE-SENSOR_TMP36"))
    )
    (comp (ref "TEMP_RING")
      (value "TMP36")
      (footprint "eagle-import:CONNECTOR_TMP36")
      (fields
        (field (name "MFR") "Analog Devices Inc.")
        (field (name "MPN") "TMP36GT9Z")
        (field (name "CREATOR") "MrSwirlyEyes")
      )
      (libsource (lib "eagle-import") (part "TEMPERATURE-SENSOR_TMP36"))
    )
    (comp (ref "TEMP_THUMB")
      (value "TMP36")
      (footprint "eagle-import:CONNECTOR_TMP36")
      (fields
        (field (name "MFR") "Analog Devices Inc.")
        (field (name "MPN") "TMP36GT9Z")
        (field (name "CREATOR") "MrSwirlyEyes")
      )
      (libsource (lib "eagle-import") (part "TEMPERATURE-SENSOR_TMP36"))
    )
    (comp (ref "VREG1")
      (value "5A/5V")
      (footprint "eagle-import:TO-263-5")
      (fields
        (field (name "MFR") "Microchip Technology")
        (field (name "MPN") "MIC29501-5.0WU")
        (field (name "CREATOR") "MrSwirlyEyes")
      )
      (libsource (lib "eagle-import") (part "VREG_MIC29501-5.0_LINEAR_ULDO_5A-5VMIC29501-5.0_5A-5V"))
    )
    (comp (ref "VREG3")
      (value "1A/3.3V")
      (footprint "eagle-import:SOIC-8_W3.9MM")
      (fields
        (field (name "MFR") "Texas Instruments")
        (field (name "MPN") "TPS76833QDR")
        (field (name "CREATOR") "MrSwirlyEyes")
      )
      (libsource (lib "eagle-import") (part "VREG_TPS76833_ULDO_FAST-TRANSIENT_1A-3.3VTPS76833QDR_1A-3.3V"))
    )
    (comp (ref "Y1")
      (value "16MHz")
      (footprint "eagle-import:CRYSTAL-SMD-5X3")
      (fields (field (name "MFR") "Abracon LLC") (field (name "MPN") "ABM3B-16.000MHZ-B2-T"))
      (libsource (lib "eagle-import") (part "CRYSTAL_ABM3B_16MHZ_18PF"))
    )
  )
  (nets
    (net (code "1") (name "5V") (class "Default")
      (node (ref "C1") (pin "1") (pinfunction "1_1") (pintype "passive"))
      (node (ref "C10") (pin "1") (pinfunction "1_1") (pintype "passive"))
      (node (ref "C11") (pin "+") (pinfunction "A_+") (pintype "passive"))
      (node (ref "C12") (pin "1") (pinfunction "1_1") (pintype "passive"))
      (node (ref "C13") (pin "+") (pinfunction "A_+") (pintype "passive"))
      (node (ref "C14") (pin "1") (pinfunction "1_1") (pintype "passive"))
      (node (ref "C15") (pin "+") (pinfunction "A_+") (pintype "passive"))
      (node (ref "C16") (pin "1") (pinfunction "1_1") (pintype "passive"))
      (node (ref "C17") (pin "+") (pinfunction "A_+") (pintype "passive"))
      (node (ref "C2") (pin "+") (pinfunction "A_+") (pintype "passive"))
      (node (ref "C20") (pin "A") (pinfunction "A_A") (pintype "passive"))
      (node (ref "C8") (pin "1") (pinfunction "1_1") (pintype "passive"))
      (node (ref "C83") (pin "1") (pinfunction "1_1") (pintype "passive"))
      (node (ref "C9") (pin "+") (pinfunction "A_+") (pintype "passive"))
      (node (ref "C94") (pin "1") (pinfunction "1_1") (pintype "passive"))
      (node (ref "D7") (pin "A") (pinfunction "A_A") (pintype "passive"))
      (node (ref "SERVO_INDEX") (pin "2") (pinfunction "VCC_2") (pintype "passive"))
      (node (ref "SERVO_MIDDLE") (pin "2") (pinfunction "VCC_2") (pintype "passive"))
      (node (ref "SERVO_PINKY") (pin "2") (pinfunction "VCC_2") (pintype "passive"))
      (node (ref "SERVO_RING") (pin "2") (pinfunction "VCC_2") (pintype "passive"))
      (node (ref "SERVO_THUMB") (pin "2") (pinfunction "VCC_2") (pintype "passive"))
      (node (ref "SERVO_WRIST") (pin "2") (pinfunction "VCC_2") (pintype "passive"))
      (node (ref "VREG1") (pin "4") (pinfunction "VOUT_4") (pintype "bidirectional"))
    )
    (net (code "2") (name "A0") (class "Default")
      (node (ref "MCU") (pin "63") (pinfunction "(ADC0/A0*)PF0_63") (pintype "bidirectional"))
    )
    (net (code "3") (name "A1") (class "Default")
      (node (ref "MCU") (pin "64") (pinfunction "(ADC1/A1*)PF1_64") (pintype "bidirectional"))
    )
    (net (code "4") (name "A2") (class "Default")
      (node (ref "MCU") (pin "1") (pinfunction "(ADC2/DIG2/A2*)PF2_1") (pintype "bidirectional"))
    )
    (net (code "5") (name "A3") (class "Default")
      (node (ref "MCU") (pin "2") (pinfunction "(ADC3/DIG4/A3*)PF3_2") (pintype "bidirectional"))
    )
    (net (code "6") (name "A4") (class "Default")
      (node (ref "MCU") (pin "3") (pinfunction "(ADC4/TCK/A4*)PF4_3") (pintype "bidirectional"))
    )
    (net (code "7") (name "A5") (class "Default")
      (node (ref "DEMUX1") (pin "1") (pinfunction "SIG_1") (pintype "passive"))
      (node (ref "MCU") (pin "4") (pinfunction "(ADC5/TMS/A5*)PF5_4") (pintype "bidirectional"))
    )
    (net (code "8") (name "A6") (class "Default")
      (node (ref "MCU") (pin "5") (pinfunction "(ADC6/TDO/A6*)PF6_5") (pintype "bidirectional"))
    )
    (net (code "9") (name "A7") (class "Default")
      (node (ref "MCU") (pin "6") (pinfunction "(ADC7/TDI/A7*)PF7_6") (pintype "bidirectional"))
    )
    (net (code "10") (name "AGND") (class "Default")
      (node (ref "ANALOG_BR") (pin "P$2") (pinfunction "P$2_P$2") (pintype "bidirectional"))
      (node (ref "C18") (pin "2") (pinfunction "2_2") (pintype "passive"))
      (node (ref "C22") (pin "2") (pinfunction "2_2") (pintype "passive"))
      (node (ref "C23") (pin "2") (pinfunction "2_2") (pintype "passive"))
      (node (ref "C24") (pin "2") (pinfunction "2_2") (pintype "passive"))
      (node (ref "C26") (pin "2") (pinfunction "2_2") (pintype "passive"))
      (node (ref "C3") (pin "2") (pinfunction "2_2") (pintype "passive"))
      (node (ref "C4") (pin "2") (pinfunction "2_2") (pintype "passive"))
      (node (ref "C47") (pin "2") (pinfunction "2_2") (pintype "passive"))
      (node (ref "C48") (pin "2") (pinfunction "2_2") (pintype "passive"))
      (node (ref "C49") (pin "2") (pinfunction "2_2") (pintype "passive"))
      (node (ref "C5") (pin "2") (pinfunction "2_2") (pintype "passive"))
      (node (ref "C50") (pin "2") (pinfunction "2_2") (pintype "passive"))
      (node (ref "C51") (pin "2") (pinfunction "2_2") (pintype "passive"))
      (node (ref "C6") (pin "2") (pinfunction "2_2") (pintype "passive"))
      (node (ref "C7") (pin "2") (pinfunction "2_2") (pintype "passive"))
      (node (ref "C85") (pin "2") (pinfunction "2_2") (pintype "passive"))
      (node (ref "DEMUX1") (pin "12") (pinfunction "GND_12") (pintype "passive"))
      (node (ref "DEMUX1") (pin "15") (pinfunction "~{EN}_15") (pintype "passive"))
      (node (ref "MCU") (pin "58") (pinfunction "AVSS_58") (pintype "bidirectional"))
      (node (ref "MCU") (pin "61") (pinfunction "AVSS_61") (pintype "bidirectional"))
      (node (ref "R16") (pin "1") (pinfunction "1_1") (pintype "passive"))
      (node (ref "R39") (pin "1") (pinfunction "1_1") (pintype "passive"))
      (node (ref "R40") (pin "1") (pinfunction "1_1") (pintype "passive"))
      (node (ref "R41") (pin "1") (pinfunction "1_1") (pintype "passive"))
      (node (ref "R42") (pin "1") (pinfunction "1_1") (pintype "passive"))
      (node (ref "TEMP_INDEX") (pin "3") (pinfunction "GND_3") (pintype "passive"))
      (node (ref "TEMP_MIDDLE") (pin "3") (pinfunction "GND_3") (pintype "passive"))
      (node (ref "TEMP_PINKY") (pin "3") (pinfunction "GND_3") (pintype "passive"))
      (node (ref "TEMP_RING") (pin "3") (pinfunction "GND_3") (pintype "passive"))
      (node (ref "TEMP_THUMB") (pin "3") (pinfunction "GND_3") (pintype "passive"))
    )
    (net (code "11") (name "AVCC") (class "Default")
      (node (ref "C18") (pin "1") (pinfunction "1_1") (pintype "passive"))
      (node (ref "C22") (pin "1") (pinfunction "1_1") (pintype "passive"))
      (node (ref "C23") (pin "1") (pinfunction "1_1") (pintype "passive"))
      (node (ref "C24") (pin "1") (pinfunction "1_1") (pintype "passive"))
      (node (ref "C26") (pin "1") (pinfunction "1_1") (pintype "passive"))
      (node (ref "C3") (pin "1") (pinfunction "1_1") (pintype "passive"))
      (node (ref "C4") (pin "1") (pinfunction "1_1") (pintype "passive"))
      (node (ref "C47") (pin "1") (pinfunction "1_1") (pintype "passive"))
      (node (ref "C48") (pin "1") (pinfunction "1_1") (pintype "passive"))
      (node (ref "C49") (pin "1") (pinfunction "1_1") (pintype "passive"))
      (node (ref "C5") (pin "1") (pinfunction "1_1") (pintype "passive"))
      (node (ref "C50") (pin "1") (pinfunction "1_1") (pintype "passive"))
      (node (ref "C51") (pin "1") (pinfunction "1_1") (pintype "passive"))
      (node (ref "C6") (pin "1") (pinfunction "1_1") (pintype "passive"))
      (node (ref "C7") (pin "1") (pinfunction "1_1") (pintype "passive"))
      (node (ref "C85") (pin "1") (pinfunction "1_1") (pintype "passive"))
      (node (ref "DEMUX1") (pin "24") (pinfunction "VCC_24") (pintype "passive"))
      (node (ref "FSR_INDEX") (pin "+") (pinfunction "+_+") (pintype "passive"))
      (node (ref "FSR_MIDDLE") (pin "+") (pinfunction "+_+") (pintype "passive"))
      (node (ref "FSR_PINKY") (pin "+") (pinfunction "+_+") (pintype "passive"))
      (node (ref "FSR_RING") (pin "+") (pinfunction "+_+") (pintype "passive"))
      (node (ref "FSR_THUMB") (pin "+") (pinfunction "+_+") (pintype "passive"))
      (node (ref "L1") (pin "2") (pinfunction "2_2") (pintype "passive"))
      (node (ref "MCU") (pin "59") (pinfunction "EVDD_59") (pintype "bidirectional"))
      (node (ref "MCU") (pin "62") (pinfunction "AREF_62") (pintype "bidirectional"))
      (node (ref "TEMP_INDEX") (pin "1") (pinfunction "VS_1") (pintype "passive"))
      (node (ref "TEMP_MIDDLE") (pin "1") (pinfunction "VS_1") (pintype "passive"))
      (node (ref "TEMP_PINKY") (pin "1") (pinfunction "VS_1") (pintype "passive"))
      (node (ref "TEMP_RING") (pin "1") (pinfunction "VS_1") (pintype "passive"))
      (node (ref "TEMP_THUMB") (pin "1") (pinfunction "VS_1") (pintype "passive"))
    )
    (net (code "12") (name "C5") (class "Default")
      (node (ref "DEMUX1") (pin "4") (pinfunction "C5_4") (pintype "passive"))
    )
    (net (code "13") (name "C6") (class "Default")
      (node (ref "DEMUX1") (pin "3") (pinfunction "C6_3") (pintype "passive"))
    )
    (net (code "14") (name "C7") (class "Default")
      (node (ref "DEMUX1") (pin "2") (pinfunction "C7_2") (pintype "passive"))
    )
    (net (code "15") (name "C8") (class "Default")
      (node (ref "DEMUX1") (pin "23") (pinfunction "C8_23") (pintype "passive"))
    )
    (net (code "16") (name "C9") (class "Default")
      (node (ref "DEMUX1") (pin "22") (pinfunction "C9_22") (pintype "passive"))
    )
    (net (code "17") (name "C10") (class "Default")
      (node (ref "DEMUX1") (pin "21") (pinfunction "C10_21") (pintype "passive"))
    )
    (net (code "18") (name "FSR_INDEX") (class "Default")
      (node (ref "DEMUX1") (pin "6") (pinfunction "C3_6") (pintype "passive"))
      (node (ref "FSR_RING") (pin "-") (pinfunction "-_-") (pintype "passive"))
      (node (ref "R39") (pin "2") (pinfunction "2_2") (pintype "passive"))
    )
    (net (code "19") (name "FSR_MIDDLE") (class "Default")
      (node (ref "DEMUX1") (pin "7") (pinfunction "C2_7") (pintype "passive"))
      (node (ref "FSR_MIDDLE") (pin "-") (pinfunction "-_-") (pintype "passive"))
      (node (ref "R40") (pin "2") (pinfunction "2_2") (pintype "passive"))
    )
    (net (code "20") (name "FSR_PINKY") (class "Default")
      (node (ref "DEMUX1") (pin "9") (pinfunction "C0_9") (pintype "passive"))
      (node (ref "FSR_THUMB") (pin "-") (pinfunction "-_-") (pintype "passive"))
      (node (ref "R42") (pin "2") (pinfunction "2_2") (pintype "passive"))
    )
    (net (code "21") (name "FSR_RING") (class "Default")
      (node (ref "DEMUX1") (pin "8") (pinfunction "C1_8") (pintype "passive"))
      (node (ref "FSR_INDEX") (pin "-") (pinfunction "-_-") (pintype "passive"))
      (node (ref "R41") (pin "2") (pinfunction "2_2") (pintype "passive"))
    )
    (net (code "22") (name "FSR_THUMB") (class "Default")
      (node (ref "DEMUX1") (pin "5") (pinfunction "C4_5") (pintype "passive"))
      (node (ref "FSR_PINKY") (pin "-") (pinfunction "-_-") (pintype "passive"))
      (node (ref "R16") (pin "2") (pinfunction "2_2") (pintype "passive"))
    )
    (net (code "23") (name "GND") (class "Default")
      (node (ref "AVR_ISP") (pin "6") (pinfunction "6_6") (pintype "passive"))
      (node (ref "B1") (pin "5") (pinfunction "GND_5") (pintype "bidirectional"))
      (node (ref "C19") (pin "2") (pinfunction "2_2") (pintype "passive"))
      (node (ref "C21") (pin "2") (pinfunction "2_2") (pintype "passive"))
      (node (ref "C25") (pin "2") (pinfunction "2_2") (pintype "passive"))
      (node (ref "C52") (pin "2") (pinfunction "2_2") (pintype "passive"))
      (node (ref "C53") (pin "2") (pinfunction "2_2") (pintype "passive"))
      (node (ref "C54") (pin "2") (pinfunction "2_2") (pintype "passive"))
      (node (ref "C55") (pin "2") (pinfunction "2_2") (pintype "passive"))
      (node (ref "C57") (pin "2") (pinfunction "2_2") (pintype "passive"))
      (node (ref "C58") (pin "2") (pinfunction "2_2") (pintype "passive"))
      (node (ref "C59") (pin "2") (pinfunction "2_2") (pintype "passive"))
      (node (ref "C60") (pin "2") (pinfunction "2_2") (pintype "passive"))
      (node (ref "C61") (pin "2") (pinfunction "2_2") (pintype "passive"))
      (node (ref "C62") (pin "2") (pinfunction "2_2") (pintype "passive"))
      (node (ref "C63") (pin "2") (pinfunction "2_2") (pintype "passive"))
      (node (ref "C80") (pin "K") (pinfunction "K_K") (pintype "passive"))
      (node (ref "C81") (pin "2") (pinfunction "2_2") (pintype "passive"))
      (node (ref "C82") (pin "2") (pinfunction "2_2") (pintype "passive"))
      (node (ref "C92") (pin "2") (pinfunction "2_2") (pintype "passive"))
      (node (ref "C93") (pin "2") (pinfunction "2_2") (pintype "passive"))
      (node (ref "C95") (pin "2") (pinfunction "2_2") (pintype "passive"))
      (node (ref "C96") (pin "2") (pinfunction "2_2") (pintype "passive"))
      (node (ref "J1") (pin "GND@1") (pinfunction "GND_GND@1") (pintype "bidirectional"))
      (node (ref "JP1") (pin "GND") (pinfunction "6_GND") (pintype "passive"))
      (node (ref "L2") (pin "1") (pinfunction "1_1") (pintype "passive"))
      (node (ref "MCU") (pin "10") (pinfunction "AVSS_RFN_10") (pintype "bidirectional"))
      (node (ref "MCU") (pin "11") (pinfunction "TST_11") (pintype "bidirectional"))
      (node (ref "MCU") (pin "20") (pinfunction "DVSS_20") (pintype "bidirectional"))
      (node (ref "MCU") (pin "24") (pinfunction "DVSS_24") (pintype "bidirectional"))
      (node (ref "MCU") (pin "33") (pinfunction "CLKI_33") (pintype "bidirectional"))
      (node (ref "MCU") (pin "35") (pinfunction "DVSS_35") (pintype "bidirectional"))
      (node (ref "MCU") (pin "45") (pinfunction "DVSS_45") (pintype "bidirectional"))
      (node (ref "MCU") (pin "55") (pinfunction "DVSS_55") (pintype "bidirectional"))
      (node (ref "MCU") (pin "7") (pinfunction "AVSS_RFP_7") (pintype "bidirectional"))
      (node (ref "NOISE_BR") (pin "P$2") (pinfunction "P$2_P$2") (pintype "bidirectional"))
      (node (ref "PWM_DRIVER") (pin "1") (pinfunction "A0_1") (pintype "passive"))
      (node (ref "PWM_DRIVER") (pin "14") (pinfunction "GND_14") (pintype "passive"))
      (node (ref "PWM_DRIVER") (pin "2") (pinfunction "A1_2") (pintype "passive"))
      (node (ref "PWM_DRIVER") (pin "23") (pinfunction "~{OE}_23") (pintype "passive"))
      (node (ref "PWM_DRIVER") (pin "24") (pinfunction "A5_24") (pintype "passive"))
      (node (ref "PWM_DRIVER") (pin "25") (pinfunction "EXTCLK_25") (pintype "passive"))
      (node (ref "PWM_DRIVER") (pin "3") (pinfunction "A2_3") (pintype "passive"))
      (node (ref "PWM_DRIVER") (pin "4") (pinfunction "A3_4") (pintype "passive"))
      (node (ref "PWM_DRIVER") (pin "5") (pinfunction "A4_5") (pintype "passive"))
      (node (ref "R1") (pin "1") (pinfunction "1_1") (pintype "passive"))
      (node (ref "R10") (pin "1") (pinfunction "1_1") (pintype "passive"))
      (node (ref "R12") (pin "1") (pinfunction "1_1") (pintype "passive"))
      (node (ref "R14") (pin "1") (pinfunction "1_1") (pintype "passive"))
      (node (ref "R2") (pin "1") (pinfunction "1_1") (pintype "passive"))
      (node (ref "R3") (pin "1") (pinfunction "1_1") (pintype "passive"))
      (node (ref "R4") (pin "1") (pinfunction "1_1") (pintype "passive"))
      (node (ref "R6") (pin "1") (pinfunction "1_1") (pintype "passive"))
      (node (ref "R8") (pin "1") (pinfunction "1_1") (pintype "passive"))
      (node (ref "S7") (pin "1") (pinfunction "1_1") (pintype "passive"))
      (node (ref "VREG3") (pin "1") (pinfunction "GND_1") (pintype "bidirectional"))
      (node (ref "VREG3") (pin "2") (pinfunction "~{EN}_2") (pintype "bidirectional"))
    )
    (net (code "24") (name "MISO") (class "Default")
      (node (ref "AVR_ISP") (pin "1") (pinfunction "1_1") (pintype "passive"))
      (node (ref "MCU") (pin "39") (pinfunction "(PDO/PCINT3/MISO/D12)PB3_39") (pintype "bidirectional"))
    )
    (net (code "25") (name "MOSI") (class "Default")
      (node (ref "AVR_ISP") (pin "4") (pinfunction "4_4") (pintype "passive"))
      (node (ref "MCU") (pin "38") (pinfunction "(PDI/PCINT2/MOSI/D11)PB2_38") (pintype "bidirectional"))
    )
    (net (code "26") (name "NGND") (class "Default")
      (node (ref "C1") (pin "2") (pinfunction "2_2") (pintype "passive"))
      (node (ref "C10") (pin "2") (pinfunction "2_2") (pintype "passive"))
      (node (ref "C11") (pin "-") (pinfunction "K_-") (pintype "passive"))
      (node (ref "C12") (pin "2") (pinfunction "2_2") (pintype "passive"))
      (node (ref "C13") (pin "-") (pinfunction "K_-") (pintype "passive"))
      (node (ref "C14") (pin "2") (pinfunction "2_2") (pintype "passive"))
      (node (ref "C15") (pin "-") (pinfunction "K_-") (pintype "passive"))
      (node (ref "C16") (pin "2") (pinfunction "2_2") (pintype "passive"))
      (node (ref "C17") (pin "-") (pinfunction "K_-") (pintype "passive"))
      (node (ref "C2") (pin "-") (pinfunction "K_-") (pintype "passive"))
      (node (ref "C20") (pin "K") (pinfunction "K_K") (pintype "passive"))
      (node (ref "C8") (pin "2") (pinfunction "2_2") (pintype "passive"))
      (node (ref "C83") (pin "2") (pinfunction "2_2") (pintype "passive"))
      (node (ref "C9") (pin "-") (pinfunction "K_-") (pintype "passive"))
      (node (ref "C94") (pin "2") (pinfunction "2_2") (pintype "passive"))
      (node (ref "C97") (pin "2") (pinfunction "2_2") (pintype "passive"))
      (node (ref "C98") (pin "2") (pinfunction "2_2") (pintype "passive"))
      (node (ref "NOISE_BR") (pin "P$1") (pinfunction "P$1_P$1") (pintype "bidirectional"))
      (node (ref "SERVO_INDEX") (pin "3") (pinfunction "GND_3") (pintype "passive"))
      (node (ref "SERVO_MIDDLE") (pin "3") (pinfunction "GND_3") (pintype "passive"))
      (node (ref "SERVO_PINKY") (pin "3") (pinfunction "GND_3") (pintype "passive"))
      (node (ref "SERVO_RING") (pin "3") (pinfunction "GND_3") (pintype "passive"))
      (node (ref "SERVO_THUMB") (pin "3") (pinfunction "GND_3") (pintype "passive"))
      (node (ref "SERVO_WRIST") (pin "3") (pinfunction "GND_3") (pintype "passive"))
      (node (ref "VREG1") (pin "3") (pinfunction "GND_3") (pintype "bidirectional"))
      (node (ref "VREG1") (pin "TAB") (pinfunction "GND_TAB") (pintype "bidirectional"))
    )
    (net (code "27") (name "Net-(A6-SIGNAL)") (class "Default")
      (node (ref "A6") (pin "FEED") (pinfunction "SIGNAL_FEED") (pintype "bidirectional"))
      (node (ref "B1") (pin "1") (pinfunction "IN_1") (pintype "bidirectional"))
      (node (ref "C62") (pin "1") (pinfunction "1_1") (pintype "passive"))
    )
    (net (code "28") (name "Net-(ANALOG_BR-PadP$1)") (class "Default")
      (node (ref "ANALOG_BR") (pin "P$1") (pinfunction "P$1_P$1") (pintype "bidirectional"))
      (node (ref "L2") (pin "2") (pinfunction "2_2") (pintype "passive"))
    )
    (net (code "29") (name "Net-(B1-GND-Pad2)") (class "Default")
      (node (ref "B1") (pin "2") (pinfunction "GND_2") (pintype "bidirectional"))
      (node (ref "C61") (pin "1") (pinfunction "1_1") (pintype "passive"))
    )
    (net (code "30") (name "Net-(B1-OUT1)") (class "Default")
      (node (ref "B1") (pin "4") (pinfunction "OUT1_4") (pintype "bidirectional"))
      (node (ref "MCU") (pin "8") (pinfunction "RFP_8") (pintype "bidirectional"))
    )
    (net (code "31") (name "Net-(B1-OUT2)") (class "Default")
      (node (ref "B1") (pin "3") (pinfunction "OUT2_3") (pintype "bidirectional"))
      (node (ref "MCU") (pin "9") (pinfunction "RFN_9") (pintype "bidirectional"))
    )
    (net (code "32") (name "Net-(BATT1-N)") (class "Default")
      (node (ref "BATT1") (pin "-") (pinfunction "N_-") (pintype "bidirectional"))
      (node (ref "J1") (pin "GND@2") (pinfunction "GND_GND@2") (pintype "bidirectional"))
    )
    (net (code "33") (name "Net-(BATT1-P)") (class "Default")
      (node (ref "BATT1") (pin "+") (pinfunction "P_+") (pintype "bidirectional"))
      (node (ref "J1") (pin "PWR") (pinfunction "PWR_PWR") (pintype "bidirectional"))
      (node (ref "SW1") (pin "2") (pinfunction "2_2") (pintype "passive"))
    )
    (net (code "34") (name "Net-(C21-Pad1)") (class "Default")
      (node (ref "C21") (pin "1") (pinfunction "1_1") (pintype "passive"))
      (node (ref "MCU") (pin "21") (pinfunction "DVDD_21") (pintype "bidirectional"))
      (node (ref "MCU") (pin "22") (pinfunction "DVDD_22") (pintype "bidirectional"))
    )
    (net (code "35") (name "Net-(JP1-2)") (class "Default")
      (node (ref "C79") (pin "1") (pinfunction "1_1") (pintype "passive"))
      (node (ref "JP1") (pin "DTR") (pinfunction "2_DTR") (pintype "passive"))
    )
    (net (code "36") (name "Net-(L3-PadK)") (class "Default")
      (node (ref "L3") (pin "K") (pinfunction "K_K") (pintype "passive"))
      (node (ref "R1") (pin "2") (pinfunction "2_2") (pintype "passive"))
    )
    (net (code "37") (name "Net-(L4-PadK)") (class "Default")
      (node (ref "L4") (pin "K") (pinfunction "K_K") (pintype "passive"))
      (node (ref "R3") (pin "2") (pinfunction "2_2") (pintype "passive"))
    )
    (net (code "38") (name "Net-(L5-PadK)") (class "Default")
      (node (ref "L5") (pin "K") (pinfunction "K_K") (pintype "passive"))
      (node (ref "R2") (pin "2") (pinfunction "2_2") (pintype "passive"))
    )
    (net (code "39") (name "Net-(MCU-AVDD)") (class "Default")
      (node (ref "C57") (pin "1") (pinfunction "1_1") (pintype "passive"))
      (node (ref "MCU") (pin "60") (pinfunction "AVDD_60") (pintype "bidirectional"))
    )
    (net (code "40") (name "Net-(MCU-XTAL1)") (class "Default")
      (node (ref "C60") (pin "1") (pinfunction "1_1") (pintype "passive"))
      (node (ref "MCU") (pin "57") (pinfunction "XTAL1_57") (pintype "bidirectional"))
      (node (ref "Y1") (pin "3") (pinfunction "2_3") (pintype "passive"))
    )
    (net (code "41") (name "Net-(MCU-XTAL2)") (class "Default")
      (node (ref "C59") (pin "1") (pinfunction "1_1") (pintype "passive"))
      (node (ref "MCU") (pin "56") (pinfunction "XTAL2_56") (pintype "bidirectional"))
      (node (ref "Y1") (pin "1") (pinfunction "1_1") (pintype "passive"))
    )
    (net (code "42") (name "Net-(SERVO_INDEX-SIG)") (class "Default")
      (node (ref "R7") (pin "1") (pinfunction "1_1") (pintype "passive"))
      (node (ref "SERVO_INDEX") (pin "1") (pinfunction "SIG_1") (pintype "passive"))
    )
    (net (code "43") (name "Net-(SERVO_MIDDLE-SIG)") (class "Default")
      (node (ref "R5") (pin "1") (pinfunction "1_1") (pintype "passive"))
      (node (ref "SERVO_MIDDLE") (pin "1") (pinfunction "SIG_1") (pintype "passive"))
    )
    (net (code "44") (name "Net-(SERVO_PINKY-SIG)") (class "Default")
      (node (ref "R13") (pin "1") (pinfunction "1_1") (pintype "passive"))
      (node (ref "SERVO_PINKY") (pin "1") (pinfunction "SIG_1") (pintype "passive"))
    )
    (net (code "45") (name "Net-(SERVO_RING-SIG)") (class "Default")
      (node (ref "R15") (pin "1") (pinfunction "1_1") (pintype "passive"))
      (node (ref "SERVO_RING") (pin "1") (pinfunction "SIG_1") (pintype "passive"))
    )
    (net (code "46") (name "Net-(SERVO_THUMB-SIG)") (class "Default")
      (node (ref "R9") (pin "1") (pinfunction "1_1") (pintype "passive"))
      (node (ref "SERVO_THUMB") (pin "1") (pinfunction "SIG_1") (pintype "passive"))
    )
    (net (code "47") (name "Net-(SERVO_WRIST-SIG)") (class "Default")
      (node (ref "R11") (pin "1") (pinfunction "1_1") (pintype "passive"))
      (node (ref "SERVO_WRIST") (pin "1") (pinfunction "SIG_1") (pintype "passive"))
    )
    (net (code "48") (name "PB4") (class "Default")
      (node (ref "MCU") (pin "40") (pinfunction "(PCINT4/OC2A/D9-PWM9)PB4_40") (pintype "bidirectional"))
    )
    (net (code "49") (name "PB5") (class "Default")
      (node (ref "MCU") (pin "41") (pinfunction "(PCINT5/OC1A/D8-PWM8)PB5_41") (pintype "bidirectional"))
    )
    (net (code "50") (name "PB6") (class "Default")
      (node (ref "L5") (pin "A") (pinfunction "A_A") (pintype "passive"))
      (node (ref "MCU") (pin "42") (pinfunction "(PCINT6/OC1B/D34-PWM34)PB6_42") (pintype "bidirectional"))
    )
    (net (code "51") (name "PB7") (class "Default")
      (node (ref "L4") (pin "A") (pinfunction "A_A") (pintype "passive"))
      (node (ref "MCU") (pin "43") (pinfunction "(PCINT7/OC0A/OC1C/D35-PWM35)PB7_43") (pintype "bidirectional"))
    )
    (net (code "52") (name "PD4") (class "Default")
      (node (ref "MCU") (pin "29") (pinfunction "(ICP1/D22)PD4_29") (pintype "bidirectional"))
    )
    (net (code "53") (name "PD5") (class "Default")
      (node (ref "MCU") (pin "30") (pinfunction "(XCK1/D23)PD5_30") (pintype "bidirectional"))
    )
    (net (code "54") (name "PD6") (class "Default")
      (node (ref "MCU") (pin "31") (pinfunction "(T1/D24)PD6_31") (pintype "bidirectional"))
    )
    (net (code "55") (name "PD7") (class "Default")
      (node (ref "MCU") (pin "32") (pinfunction "(T0/D25)PD7_32") (pintype "bidirectional"))
    )
    (net (code "56") (name "PE2") (class "Default")
      (node (ref "DEMUX1") (pin "10") (pinfunction "S0_10") (pintype "passive"))
      (node (ref "MCU") (pin "48") (pinfunction "(XCK0/AIN0/D2)PE2_48") (pintype "bidirectional"))
    )
    (net (code "57") (name "PE3") (class "Default")
      (node (ref "MCU") (pin "49") (pinfunction "(AIN1/OC3A/D3-PWM3)PE3_49") (pintype "bidirectional"))
    )
    (net (code "58") (name "PE4") (class "Default")
      (node (ref "MCU") (pin "50") (pinfunction "(INT4/OC3B/D4-PWM4)PE4_50") (pintype "bidirectional"))
    )
    (net (code "59") (name "PE5") (class "Default")
      (node (ref "MCU") (pin "51") (pinfunction "(INT5/OC3C/D5-PWM5)PE5_51") (pintype "bidirectional"))
    )
    (net (code "60") (name "PE6") (class "Default")
      (node (ref "DEMUX1") (pin "11") (pinfunction "S1_11") (pintype "passive"))
      (node (ref "MCU") (pin "52") (pinfunction "(T3/INT6/D6)PE6_52") (pintype "bidirectional"))
    )
    (net (code "61") (name "PE7") (class "Default")
      (node (ref "DEMUX1") (pin "14") (pinfunction "S2_14") (pintype "passive"))
      (node (ref "MCU") (pin "53") (pinfunction "(ICP3/INT7/CLKO/D7)PE7_53") (pintype "bidirectional"))
    )
    (net (code "62") (name "PG0") (class "Default")
      (node (ref "MCU") (pin "14") (pinfunction "(DIG3/D16)PG0_14") (pintype "bidirectional"))
    )
    (net (code "63") (name "PG1") (class "Default")
      (node (ref "MCU") (pin "15") (pinfunction "(DIG1/D17)PG1_15") (pintype "bidirectional"))
    )
    (net (code "64") (name "PG2") (class "Default")
      (node (ref "MCU") (pin "16") (pinfunction "(AMR/D18)PG2_16") (pintype "bidirectional"))
    )
    (net (code "65") (name "PG3") (class "Default")
      (node (ref "MCU") (pin "17") (pinfunction "(TOSC2)PG3_17") (pintype "bidirectional"))
    )
    (net (code "66") (name "PG4") (class "Default")
      (node (ref "MCU") (pin "18") (pinfunction "(TOSC1)PG4_18") (pintype "bidirectional"))
    )
    (net (code "67") (name "PG5") (class "Default")
      (node (ref "MCU") (pin "19") (pinfunction "(OC0B/D19-PWM19)PG5_19") (pintype "bidirectional"))
    )
    (net (code "68") (name "PWM6") (class "Default")
      (node (ref "PWM_DRIVER") (pin "12") (pinfunction "PWM6_12") (pintype "passive"))
    )
    (net (code "69") (name "PWM7") (class "Default")
      (node (ref "PWM_DRIVER") (pin "13") (pinfunction "PWM7_13") (pintype "passive"))
    )
    (net (code "70") (name "PWM8") (class "Default")
      (node (ref "PWM_DRIVER") (pin "15") (pinfunction "PWM8_15") (pintype "passive"))
    )
    (net (code "71") (name "PWM9") (class "Default")
      (node (ref "PWM_DRIVER") (pin "16") (pinfunction "PWM9_16") (pintype "passive"))
    )
    (net (code "72") (name "PWM10") (class "Default")
      (node (ref "PWM_DRIVER") (pin "17") (pinfunction "PWM10_17") (pintype "passive"))
    )
    (net (code "73") (name "PWM11") (class "Default")
      (node (ref "PWM_DRIVER") (pin "18") (pinfunction "PWM11_18") (pintype "passive"))
    )
    (net (code "74") (name "PWM12") (class "Default")
      (node (ref "PWM_DRIVER") (pin "19") (pinfunction "PWM12_19") (pintype "passive"))
    )
    (net (code "75") (name "PWM13") (class "Default")
      (node (ref "PWM_DRIVER") (pin "20") (pinfunction "PWM13_20") (pintype "passive"))
    )
    (net (code "76") (name "PWM14") (class "Default")
      (node (ref "PWM_DRIVER") (pin "21") (pinfunction "PWM14_21") (pintype "passive"))
    )
    (net (code "77") (name "PWM15") (class "Default")
      (node (ref "PWM_DRIVER") (pin "22") (pinfunction "PWM15_22") (pintype "passive"))
    )
    (net (code "78") (name "RESET") (class "Default")
      (node (ref "AVR_ISP") (pin "5") (pinfunction "5_5") (pintype "passive"))
      (node (ref "C79") (pin "2") (pinfunction "2_2") (pintype "passive"))
      (node (ref "D1") (pin "A") (pinfunction "A_A") (pintype "passive"))
      (node (ref "MCU") (pin "12") (pinfunction "RSTN_12") (pintype "bidirectional"))
      (node (ref "R43") (pin "1") (pinfunction "1_1") (pintype "passive"))
      (node (ref "S7") (pin "3") (pinfunction "2_3") (pintype "passive"))
    )
    (net (code "79") (name "RX0") (class "Default")
      (node (ref "JP1") (pin "TXO") (pinfunction "4_TXO") (pintype "passive"))
      (node (ref "MCU") (pin "46") (pinfunction "(PCINT8/RXD0/D0)PE0_46") (pintype "bidirectional"))
    )
    (net (code "80") (name "RX1") (class "Default")
      (node (ref "MCU") (pin "27") (pinfunction "(INT2/RXD1/D20)PD2_27") (pintype "bidirectional"))
    )
    (net (code "81") (name "SCK") (class "Default")
      (node (ref "AVR_ISP") (pin "3") (pinfunction "3_3") (pintype "passive"))
      (node (ref "MCU") (pin "37") (pinfunction "(PCINT1/SCK/D13)PB1_37") (pintype "bidirectional"))
    )
    (net (code "82") (name "SCL") (class "Default")
      (node (ref "MCU") (pin "25") (pinfunction "(INT0/SCL/D15)PD0_25") (pintype "bidirectional"))
      (node (ref "PWM_DRIVER") (pin "26") (pinfunction "SCL_26") (pintype "passive"))
      (node (ref "R17") (pin "1") (pinfunction "1_1") (pintype "passive"))
    )
    (net (code "83") (name "SDA") (class "Default")
      (node (ref "MCU") (pin "26") (pinfunction "(INT1/SDA/D14)PD1_26") (pintype "bidirectional"))
      (node (ref "PWM_DRIVER") (pin "27") (pinfunction "SDA_27") (pintype "passive"))
      (node (ref "R18") (pin "1") (pinfunction "1_1") (pintype "passive"))
    )
    (net (code "84") (name "SERVO_INDEX") (class "Default")
      (node (ref "PWM_DRIVER") (pin "9") (pinfunction "PWM3_9") (pintype "passive"))
      (node (ref "R6") (pin "2") (pinfunction "2_2") (pintype "passive"))
      (node (ref "R7") (pin "2") (pinfunction "2_2") (pintype "passive"))
    )
    (net (code "85") (name "SERVO_MIDDLE") (class "Default")
      (node (ref "PWM_DRIVER") (pin "8") (pinfunction "PWM2_8") (pintype "passive"))
      (node (ref "R4") (pin "2") (pinfunction "2_2") (pintype "passive"))
      (node (ref "R5") (pin "2") (pinfunction "2_2") (pintype "passive"))
    )
    (net (code "86") (name "SERVO_PINKY") (class "Default")
      (node (ref "PWM_DRIVER") (pin "6") (pinfunction "PWM0_6") (pintype "passive"))
      (node (ref "R12") (pin "2") (pinfunction "2_2") (pintype "passive"))
      (node (ref "R13") (pin "2") (pinfunction "2_2") (pintype "passive"))
    )
    (net (code "87") (name "SERVO_RING") (class "Default")
      (node (ref "PWM_DRIVER") (pin "7") (pinfunction "PWM1_7") (pintype "passive"))
      (node (ref "R14") (pin "2") (pinfunction "2_2") (pintype "passive"))
      (node (ref "R15") (pin "2") (pinfunction "2_2") (pintype "passive"))
    )
    (net (code "88") (name "SERVO_THUMB") (class "Default")
      (node (ref "PWM_DRIVER") (pin "10") (pinfunction "PWM4_10") (pintype "passive"))
      (node (ref "R8") (pin "2") (pinfunction "2_2") (pintype "passive"))
      (node (ref "R9") (pin "2") (pinfunction "2_2") (pintype "passive"))
    )
    (net (code "89") (name "SERVO_WRIST") (class "Default")
      (node (ref "PWM_DRIVER") (pin "11") (pinfunction "PWM5_11") (pintype "passive"))
      (node (ref "R10") (pin "2") (pinfunction "2_2") (pintype "passive"))
      (node (ref "R11") (pin "2") (pinfunction "2_2") (pintype "passive"))
    )
    (net (code "90") (name "SSN") (class "Default")
      (node (ref "DEMUX1") (pin "13") (pinfunction "S3_13") (pintype "passive"))
      (node (ref "MCU") (pin "36") (pinfunction "(PCINT0/SSN/D10)PB0_36") (pintype "bidirectional"))
    )
    (net (code "91") (name "TEMP_INDEX") (class "Default")
      (node (ref "DEMUX1") (pin "17") (pinfunction "C14_17") (pintype "passive"))
      (node (ref "TEMP_RING") (pin "2") (pinfunction "VOUT_2") (pintype "passive"))
    )
    (net (code "92") (name "TEMP_MIDDLE") (class "Default")
      (node (ref "DEMUX1") (pin "18") (pinfunction "C13_18") (pintype "passive"))
      (node (ref "TEMP_MIDDLE") (pin "2") (pinfunction "VOUT_2") (pintype "passive"))
    )
    (net (code "93") (name "TEMP_PINKY") (class "Default")
      (node (ref "DEMUX1") (pin "20") (pinfunction "C11_20") (pintype "passive"))
      (node (ref "TEMP_THUMB") (pin "2") (pinfunction "VOUT_2") (pintype "passive"))
    )
    (net (code "94") (name "TEMP_RING") (class "Default")
      (node (ref "DEMUX1") (pin "19") (pinfunction "C12_19") (pintype "passive"))
      (node (ref "TEMP_INDEX") (pin "2") (pinfunction "VOUT_2") (pintype "passive"))
    )
    (net (code "95") (name "TEMP_THUMB") (class "Default")
      (node (ref "DEMUX1") (pin "16") (pinfunction "C15_16") (pintype "passive"))
      (node (ref "TEMP_PINKY") (pin "2") (pinfunction "VOUT_2") (pintype "passive"))
    )
    (net (code "96") (name "TX0") (class "Default")
      (node (ref "JP1") (pin "RXI") (pinfunction "3_RXI") (pintype "passive"))
      (node (ref "MCU") (pin "47") (pinfunction "(TXD0/D1)PE1_47") (pintype "bidirectional"))
    )
    (net (code "97") (name "TX1") (class "Default")
      (node (ref "MCU") (pin "28") (pinfunction "(INT3/TXD1/D21)PD3_28") (pintype "bidirectional"))
    )
    (net (code "98") (name "VBATT") (class "Default")
      (node (ref "C80") (pin "A") (pinfunction "A_A") (pintype "passive"))
      (node (ref "C81") (pin "1") (pinfunction "1_1") (pintype "passive"))
      (node (ref "C82") (pin "1") (pinfunction "1_1") (pintype "passive"))
      (node (ref "C95") (pin "1") (pinfunction "1_1") (pintype "passive"))
      (node (ref "C96") (pin "1") (pinfunction "1_1") (pintype "passive"))
      (node (ref "C97") (pin "1") (pinfunction "1_1") (pintype "passive"))
      (node (ref "C98") (pin "1") (pinfunction "1_1") (pintype "passive"))
      (node (ref "D6") (pin "K") (pinfunction "K_K") (pintype "passive"))
      (node (ref "D7") (pin "K") (pinfunction "K_K") (pintype "passive"))
      (node (ref "L3") (pin "A") (pinfunction "A_A") (pintype "passive"))
      (node (ref "SW1") (pin "1") (pinfunction "1_1") (pintype "passive"))
      (node (ref "VREG1") (pin "1") (pinfunction "EN_1") (pintype "bidirectional"))
      (node (ref "VREG1") (pin "2") (pinfunction "VIN_2") (pintype "bidirectional"))
      (node (ref "VREG3") (pin "3") (pinfunction "VIN_3") (pintype "bidirectional"))
      (node (ref "VREG3") (pin "4") (pinfunction "VIN_4") (pintype "bidirectional"))
    )
    (net (code "99") (name "VCC") (class "Default")
      (node (ref "AVR_ISP") (pin "2") (pinfunction "2_2") (pintype "passive"))
      (node (ref "C19") (pin "1") (pinfunction "1_1") (pintype "passive"))
      (node (ref "C25") (pin "1") (pinfunction "1_1") (pintype "passive"))
      (node (ref "C52") (pin "1") (pinfunction "1_1") (pintype "passive"))
      (node (ref "C53") (pin "1") (pinfunction "1_1") (pintype "passive"))
      (node (ref "C54") (pin "1") (pinfunction "1_1") (pintype "passive"))
      (node (ref "C55") (pin "1") (pinfunction "1_1") (pintype "passive"))
      (node (ref "C58") (pin "1") (pinfunction "1_1") (pintype "passive"))
      (node (ref "C63") (pin "1") (pinfunction "1_1") (pintype "passive"))
      (node (ref "C92") (pin "1") (pinfunction "1_1") (pintype "passive"))
      (node (ref "C93") (pin "1") (pinfunction "1_1") (pintype "passive"))
      (node (ref "D1") (pin "K") (pinfunction "K_K") (pintype "passive"))
      (node (ref "D6") (pin "A") (pinfunction "A_A") (pintype "passive"))
      (node (ref "JP1") (pin "VCC") (pinfunction "1_VCC") (pintype "passive"))
      (node (ref "L1") (pin "1") (pinfunction "1_1") (pintype "passive"))
      (node (ref "MCU") (pin "23") (pinfunction "DEVDD_23") (pintype "bidirectional"))
      (node (ref "MCU") (pin "34") (pinfunction "DEVDD_34") (pintype "bidirectional"))
      (node (ref "MCU") (pin "44") (pinfunction "DEVDD_44") (pintype "bidirectional"))
      (node (ref "MCU") (pin "54") (pinfunction "DEVDD_54") (pintype "bidirectional"))
      (node (ref "PWM_DRIVER") (pin "28") (pinfunction "VCC_28") (pintype "passive"))
      (node (ref "R17") (pin "2") (pinfunction "2_2") (pintype "passive"))
      (node (ref "R18") (pin "2") (pinfunction "2_2") (pintype "passive"))
      (node (ref "R43") (pin "2") (pinfunction "2_2") (pintype "passive"))
      (node (ref "VREG3") (pin "5") (pinfunction "VOUT_5") (pintype "bidirectional"))
      (node (ref "VREG3") (pin "6") (pinfunction "VOUT_6") (pintype "bidirectional"))
    )
    (net (code "100") (name "unconnected-(JP1-5-PadCTS)") (class "Default")
      (node (ref "JP1") (pin "CTS") (pinfunction "5_CTS") (pintype "passive"))
    )
    (net (code "101") (name "unconnected-(MCU-RSTON-Pad13)") (class "Default")
      (node (ref "MCU") (pin "13") (pinfunction "RSTON_13") (pintype "bidirectional"))
    )
    (net (code "102") (name "unconnected-(SW1-Pad3)") (class "Default")
      (node (ref "SW1") (pin "3") (pinfunction "3_3") (pintype "passive"))
    )
    (net (code "103") (name "unconnected-(VREG1-FLG-Pad5)") (class "Default")
      (node (ref "VREG1") (pin "5") (pinfunction "FLG_5") (pintype "bidirectional"))
    )
    (net (code "104") (name "unconnected-(VREG3-FB{slash}NC-Pad7)") (class "Default")
      (node (ref "VREG3") (pin "7") (pinfunction "FB/NC_7") (pintype "bidirectional"))
    )
    (net (code "105") (name "unconnected-(VREG3-PG-Pad8)") (class "Default")
      (node (ref "VREG3") (pin "8") (pinfunction "PG_8") (pintype "bidirectional"))
    )
  )
)
